# CNC.net
KiCad netlist of a schematic drawn in Altium Designer
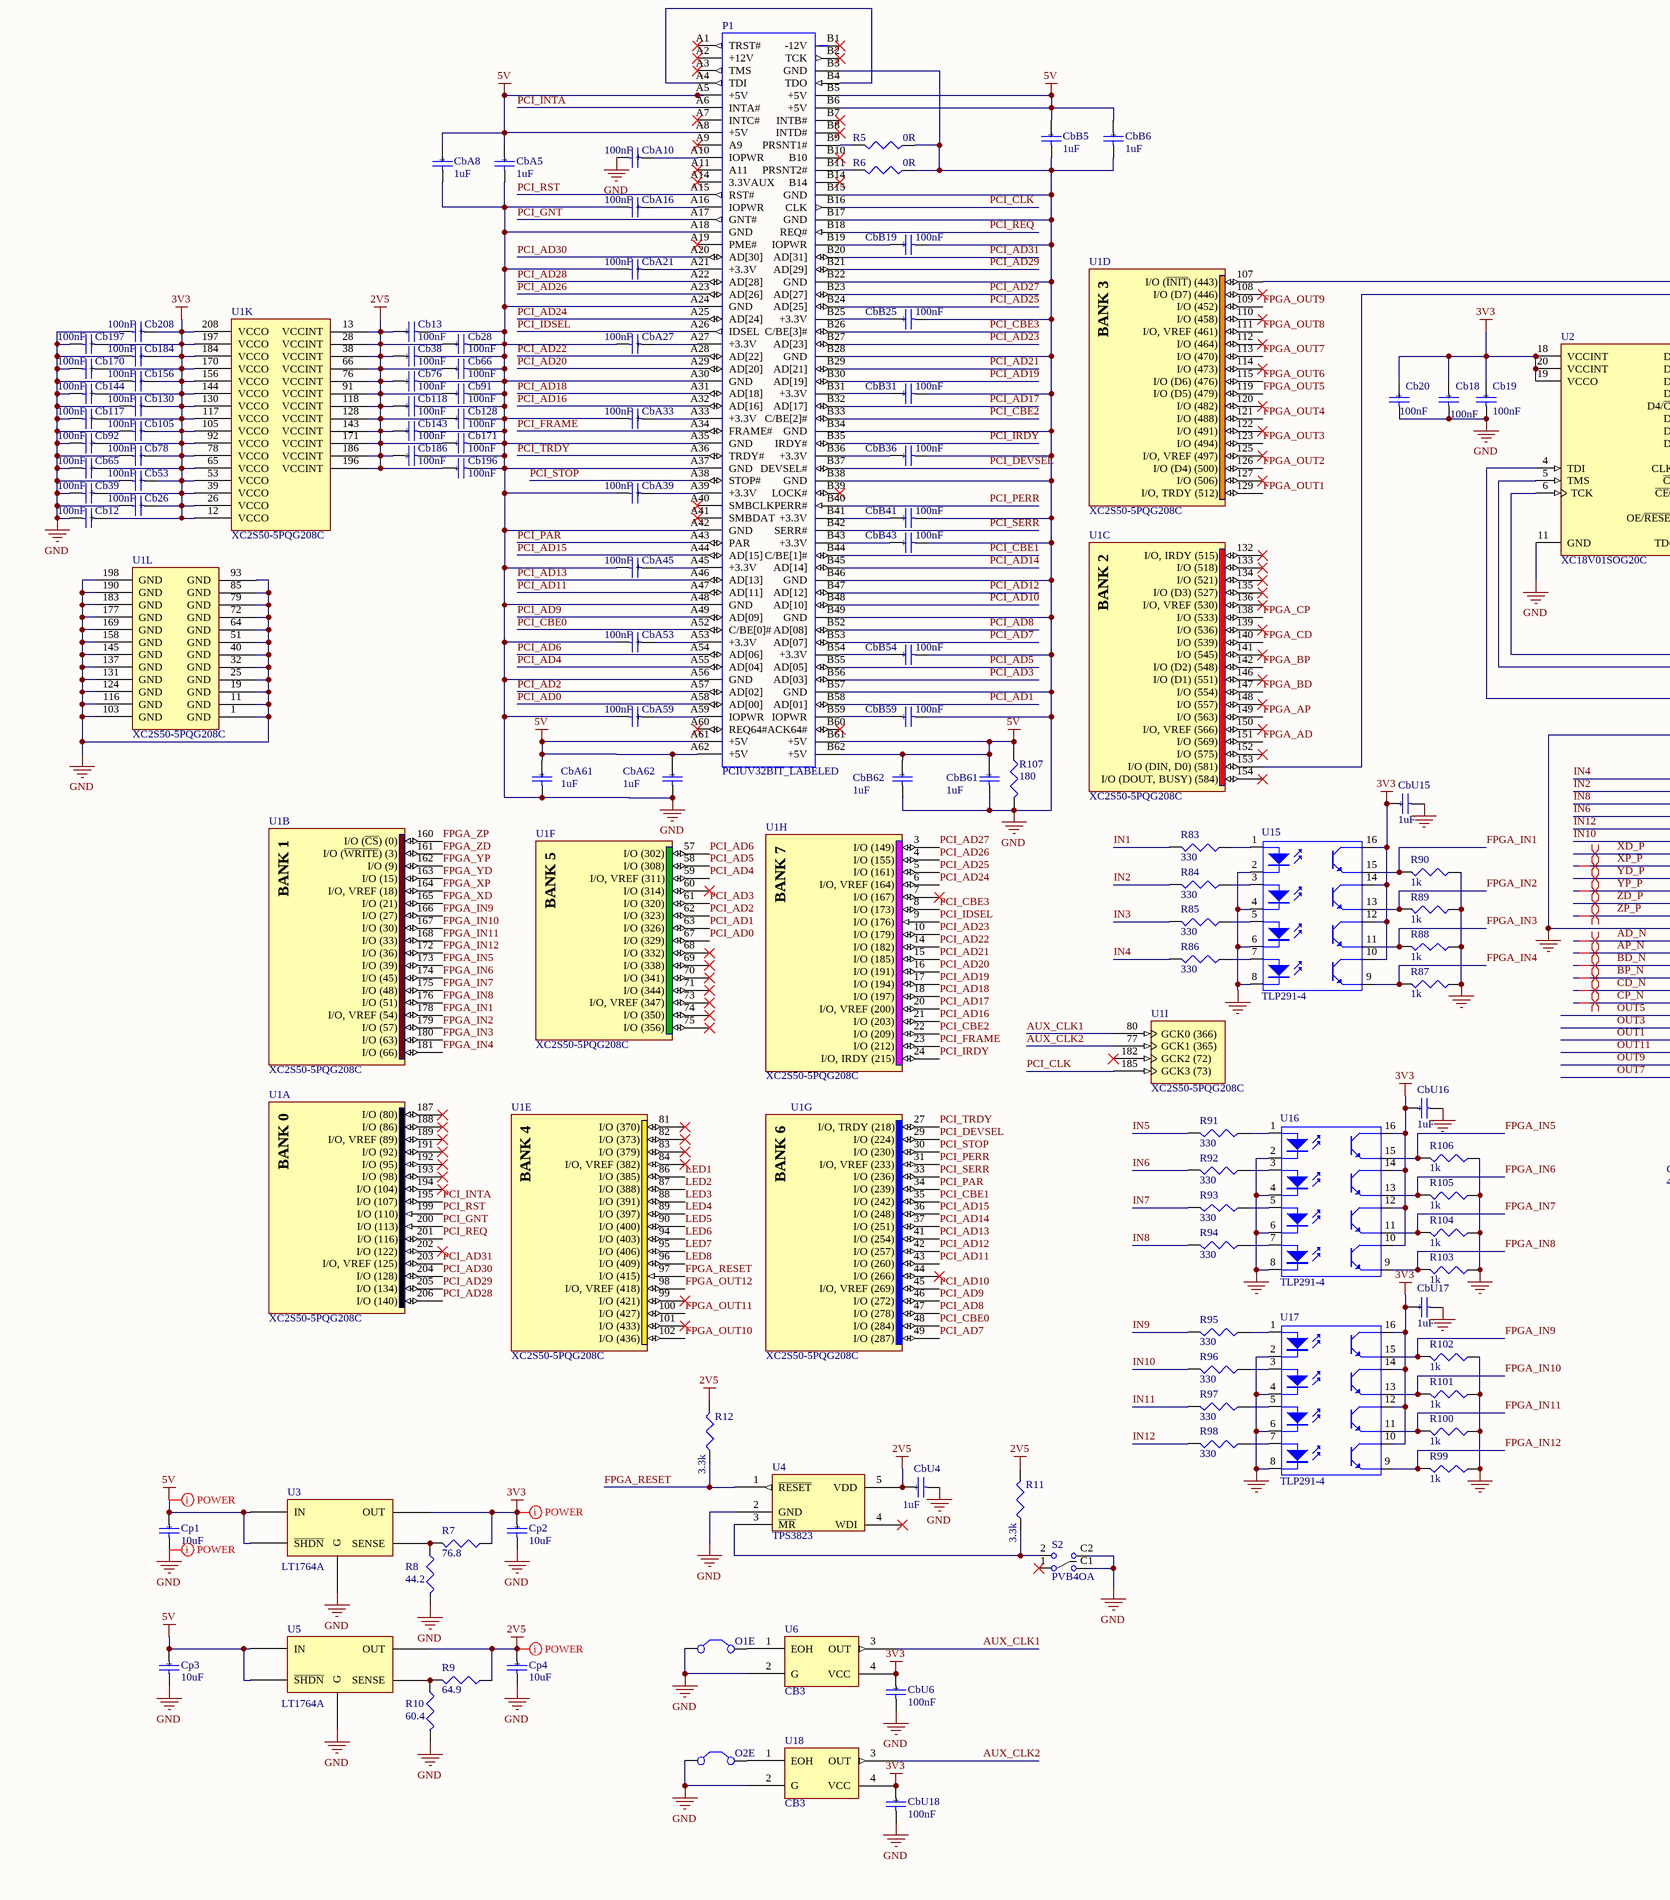
[diagram p0: CNC.SchDoc, bottom left]
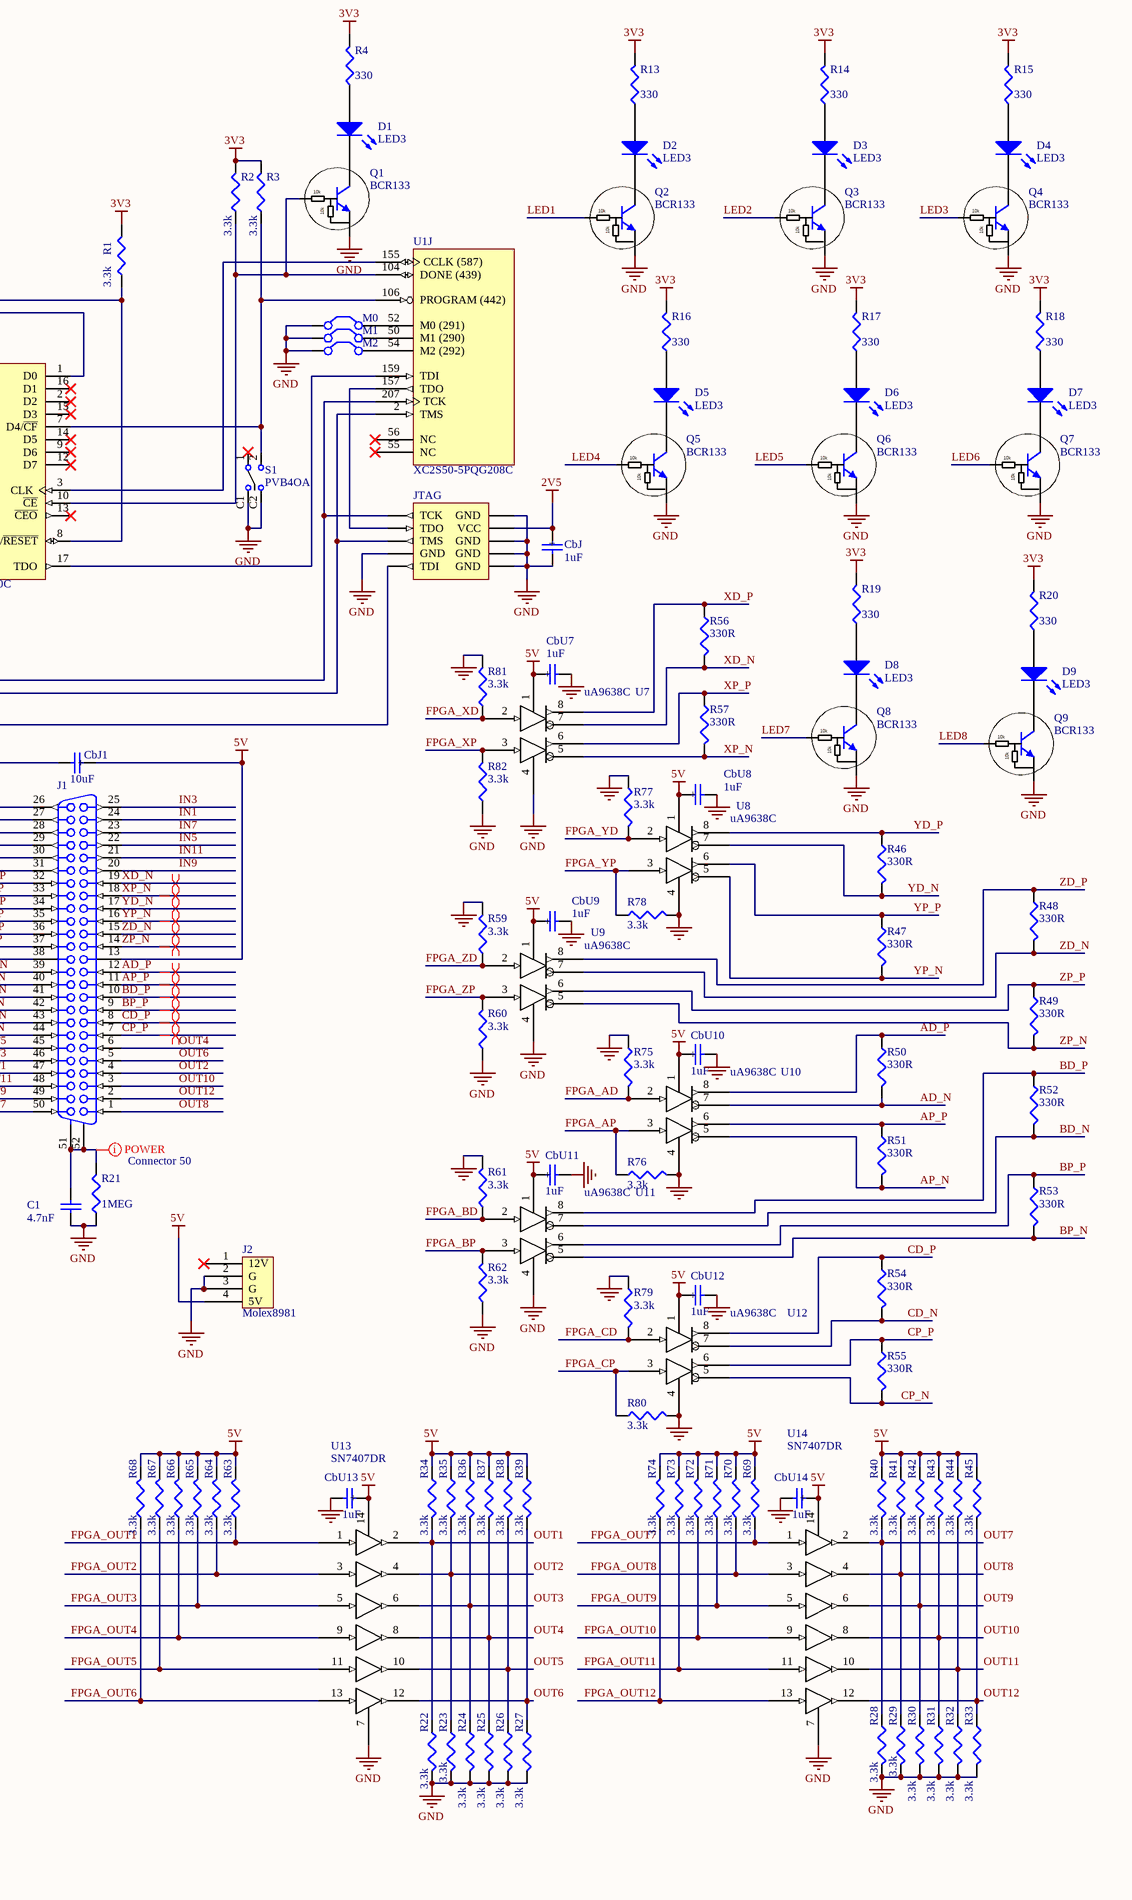
[diagram p1: CNC.SchDoc, bottom right]

(export (version "E")
  (design (tool "Eeschema 10.0.6"))
  (components
    (comp (ref "C1")
      (value "4.7nF")
      (footprint "C1206")
      (description "Capacitor (Semiconductor SIM Model)")
      (fields (field (name "PUBLISHER") "Altium Limited"))
      (libsource (lib "") (part "Cap Semi_1"))
    )
    (comp (ref "Cb12")
      (value "100nF")
      (footprint "C1206_POL")
      (description "Capacitor (Semiconductor SIM Model)")
      (fields (field (name "PUBLISHER") "Altium Limited"))
      (libsource (lib "Miscellaneous Devices") (part "Cap Semi"))
    )
    (comp (ref "Cb13")
      (value "100nF")
      (footprint "C1206_POL")
      (description "Capacitor (Semiconductor SIM Model)")
      (fields (field (name "PUBLISHER") "Altium Limited"))
      (libsource (lib "Miscellaneous Devices") (part "Cap Semi"))
    )
    (comp (ref "Cb18")
      (value "100nF")
      (footprint "C1206_POL")
      (description "Capacitor (Semiconductor SIM Model)")
      (fields (field (name "PUBLISHER") "Altium Limited"))
      (libsource (lib "Miscellaneous Devices") (part "Cap Semi"))
    )
    (comp (ref "Cb19")
      (value "100nF")
      (footprint "C1206_POL")
      (description "Capacitor (Semiconductor SIM Model)")
      (fields (field (name "PUBLISHER") "Altium Limited"))
      (libsource (lib "Miscellaneous Devices") (part "Cap Semi"))
    )
    (comp (ref "Cb20")
      (value "100nF")
      (footprint "C1206_POL")
      (description "Capacitor (Semiconductor SIM Model)")
      (fields (field (name "PUBLISHER") "Altium Limited"))
      (libsource (lib "Miscellaneous Devices") (part "Cap Semi"))
    )
    (comp (ref "Cb26")
      (value "100nF")
      (footprint "C1206_POL")
      (description "Capacitor (Semiconductor SIM Model)")
      (fields (field (name "PUBLISHER") "Altium Limited"))
      (libsource (lib "Miscellaneous Devices") (part "Cap Semi"))
    )
    (comp (ref "Cb28")
      (value "100nF")
      (footprint "C1206_POL")
      (description "Capacitor (Semiconductor SIM Model)")
      (fields (field (name "PUBLISHER") "Altium Limited"))
      (libsource (lib "Miscellaneous Devices") (part "Cap Semi"))
    )
    (comp (ref "Cb38")
      (value "100nF")
      (footprint "C1206_POL")
      (description "Capacitor (Semiconductor SIM Model)")
      (fields (field (name "PUBLISHER") "Altium Limited"))
      (libsource (lib "Miscellaneous Devices") (part "Cap Semi"))
    )
    (comp (ref "Cb39")
      (value "100nF")
      (footprint "C1206_POL")
      (description "Capacitor (Semiconductor SIM Model)")
      (fields (field (name "PUBLISHER") "Altium Limited"))
      (libsource (lib "Miscellaneous Devices") (part "Cap Semi"))
    )
    (comp (ref "Cb53")
      (value "100nF")
      (footprint "C1206_POL")
      (description "Capacitor (Semiconductor SIM Model)")
      (fields (field (name "PUBLISHER") "Altium Limited"))
      (libsource (lib "Miscellaneous Devices") (part "Cap Semi"))
    )
    (comp (ref "Cb65")
      (value "100nF")
      (footprint "C1206_POL")
      (description "Capacitor (Semiconductor SIM Model)")
      (fields (field (name "PUBLISHER") "Altium Limited"))
      (libsource (lib "Miscellaneous Devices") (part "Cap Semi"))
    )
    (comp (ref "Cb66")
      (value "100nF")
      (footprint "C1206_POL")
      (description "Capacitor (Semiconductor SIM Model)")
      (fields (field (name "PUBLISHER") "Altium Limited"))
      (libsource (lib "Miscellaneous Devices") (part "Cap Semi"))
    )
    (comp (ref "Cb76")
      (value "100nF")
      (footprint "C1206_POL")
      (description "Capacitor (Semiconductor SIM Model)")
      (fields (field (name "PUBLISHER") "Altium Limited"))
      (libsource (lib "Miscellaneous Devices") (part "Cap Semi"))
    )
    (comp (ref "Cb78")
      (value "100nF")
      (footprint "C1206_POL")
      (description "Capacitor (Semiconductor SIM Model)")
      (fields (field (name "PUBLISHER") "Altium Limited"))
      (libsource (lib "Miscellaneous Devices") (part "Cap Semi"))
    )
    (comp (ref "Cb91")
      (value "100nF")
      (footprint "C1206_POL")
      (description "Capacitor (Semiconductor SIM Model)")
      (fields (field (name "PUBLISHER") "Altium Limited"))
      (libsource (lib "Miscellaneous Devices") (part "Cap Semi"))
    )
    (comp (ref "Cb92")
      (value "100nF")
      (footprint "C1206_POL")
      (description "Capacitor (Semiconductor SIM Model)")
      (fields (field (name "PUBLISHER") "Altium Limited"))
      (libsource (lib "Miscellaneous Devices") (part "Cap Semi"))
    )
    (comp (ref "Cb105")
      (value "100nF")
      (footprint "C1206_POL")
      (description "Capacitor (Semiconductor SIM Model)")
      (fields (field (name "PUBLISHER") "Altium Limited"))
      (libsource (lib "Miscellaneous Devices") (part "Cap Semi"))
    )
    (comp (ref "Cb117")
      (value "100nF")
      (footprint "C1206_POL")
      (description "Capacitor (Semiconductor SIM Model)")
      (fields (field (name "PUBLISHER") "Altium Limited"))
      (libsource (lib "Miscellaneous Devices") (part "Cap Semi"))
    )
    (comp (ref "Cb118")
      (value "100nF")
      (footprint "C1206_POL")
      (description "Capacitor (Semiconductor SIM Model)")
      (fields (field (name "PUBLISHER") "Altium Limited"))
      (libsource (lib "Miscellaneous Devices") (part "Cap Semi"))
    )
    (comp (ref "Cb128")
      (value "100nF")
      (footprint "C1206_POL")
      (description "Capacitor (Semiconductor SIM Model)")
      (fields (field (name "PUBLISHER") "Altium Limited"))
      (libsource (lib "Miscellaneous Devices") (part "Cap Semi"))
    )
    (comp (ref "Cb130")
      (value "100nF")
      (footprint "C1206_POL")
      (description "Capacitor (Semiconductor SIM Model)")
      (fields (field (name "PUBLISHER") "Altium Limited"))
      (libsource (lib "Miscellaneous Devices") (part "Cap Semi"))
    )
    (comp (ref "Cb143")
      (value "100nF")
      (footprint "C1206_POL")
      (description "Capacitor (Semiconductor SIM Model)")
      (fields (field (name "PUBLISHER") "Altium Limited"))
      (libsource (lib "Miscellaneous Devices") (part "Cap Semi"))
    )
    (comp (ref "Cb144")
      (value "100nF")
      (footprint "C1206_POL")
      (description "Capacitor (Semiconductor SIM Model)")
      (fields (field (name "PUBLISHER") "Altium Limited"))
      (libsource (lib "Miscellaneous Devices") (part "Cap Semi"))
    )
    (comp (ref "Cb156")
      (value "100nF")
      (footprint "C1206_POL")
      (description "Capacitor (Semiconductor SIM Model)")
      (fields (field (name "PUBLISHER") "Altium Limited"))
      (libsource (lib "Miscellaneous Devices") (part "Cap Semi"))
    )
    (comp (ref "Cb170")
      (value "100nF")
      (footprint "C1206_POL")
      (description "Capacitor (Semiconductor SIM Model)")
      (fields (field (name "PUBLISHER") "Altium Limited"))
      (libsource (lib "Miscellaneous Devices") (part "Cap Semi"))
    )
    (comp (ref "Cb171")
      (value "100nF")
      (footprint "C1206_POL")
      (description "Capacitor (Semiconductor SIM Model)")
      (fields (field (name "PUBLISHER") "Altium Limited"))
      (libsource (lib "Miscellaneous Devices") (part "Cap Semi"))
    )
    (comp (ref "Cb184")
      (value "100nF")
      (footprint "C1206_POL")
      (description "Capacitor (Semiconductor SIM Model)")
      (fields (field (name "PUBLISHER") "Altium Limited"))
      (libsource (lib "Miscellaneous Devices") (part "Cap Semi"))
    )
    (comp (ref "Cb186")
      (value "100nF")
      (footprint "C1206_POL")
      (description "Capacitor (Semiconductor SIM Model)")
      (fields (field (name "PUBLISHER") "Altium Limited"))
      (libsource (lib "Miscellaneous Devices") (part "Cap Semi"))
    )
    (comp (ref "Cb196")
      (value "100nF")
      (footprint "C1206_POL")
      (description "Capacitor (Semiconductor SIM Model)")
      (fields (field (name "PUBLISHER") "Altium Limited"))
      (libsource (lib "Miscellaneous Devices") (part "Cap Semi"))
    )
    (comp (ref "Cb197")
      (value "100nF")
      (footprint "C1206_POL")
      (description "Capacitor (Semiconductor SIM Model)")
      (fields (field (name "PUBLISHER") "Altium Limited"))
      (libsource (lib "Miscellaneous Devices") (part "Cap Semi"))
    )
    (comp (ref "Cb208")
      (value "100nF")
      (footprint "C1206_POL")
      (description "Capacitor (Semiconductor SIM Model)")
      (fields (field (name "PUBLISHER") "Altium Limited"))
      (libsource (lib "Miscellaneous Devices") (part "Cap Semi"))
    )
    (comp (ref "CbA5")
      (value "1uF")
      (footprint "C1206_POL")
      (description "Capacitor (Semiconductor SIM Model)")
      (fields (field (name "PUBLISHER") "Altium Limited"))
      (libsource (lib "Miscellaneous Devices") (part "Cap Semi"))
    )
    (comp (ref "CbA8")
      (value "1uF")
      (footprint "C1206_POL")
      (description "Capacitor (Semiconductor SIM Model)")
      (fields (field (name "PUBLISHER") "Altium Limited"))
      (libsource (lib "Miscellaneous Devices") (part "Cap Semi"))
    )
    (comp (ref "CbA10")
      (value "100nF")
      (footprint "C1206_POL")
      (description "Capacitor (Semiconductor SIM Model)")
      (fields (field (name "PUBLISHER") "Altium Limited"))
      (libsource (lib "Miscellaneous Devices") (part "Cap Semi"))
    )
    (comp (ref "CbA16")
      (value "100nF")
      (footprint "C1206_POL")
      (description "Capacitor (Semiconductor SIM Model)")
      (fields (field (name "PUBLISHER") "Altium Limited"))
      (libsource (lib "Miscellaneous Devices") (part "Cap Semi"))
    )
    (comp (ref "CbA21")
      (value "100nF")
      (footprint "C1206_POL")
      (description "Capacitor (Semiconductor SIM Model)")
      (fields (field (name "PUBLISHER") "Altium Limited"))
      (libsource (lib "Miscellaneous Devices") (part "Cap Semi"))
    )
    (comp (ref "CbA27")
      (value "100nF")
      (footprint "C1206_POL")
      (description "Capacitor (Semiconductor SIM Model)")
      (fields (field (name "PUBLISHER") "Altium Limited"))
      (libsource (lib "Miscellaneous Devices") (part "Cap Semi"))
    )
    (comp (ref "CbA33")
      (value "100nF")
      (footprint "C1206_POL")
      (description "Capacitor (Semiconductor SIM Model)")
      (fields (field (name "PUBLISHER") "Altium Limited"))
      (libsource (lib "Miscellaneous Devices") (part "Cap Semi"))
    )
    (comp (ref "CbA39")
      (value "100nF")
      (footprint "C1206_POL")
      (description "Capacitor (Semiconductor SIM Model)")
      (fields (field (name "PUBLISHER") "Altium Limited"))
      (libsource (lib "Miscellaneous Devices") (part "Cap Semi"))
    )
    (comp (ref "CbA45")
      (value "100nF")
      (footprint "C1206_POL")
      (description "Capacitor (Semiconductor SIM Model)")
      (fields (field (name "PUBLISHER") "Altium Limited"))
      (libsource (lib "Miscellaneous Devices") (part "Cap Semi"))
    )
    (comp (ref "CbA53")
      (value "100nF")
      (footprint "C1206_POL")
      (description "Capacitor (Semiconductor SIM Model)")
      (fields (field (name "PUBLISHER") "Altium Limited"))
      (libsource (lib "Miscellaneous Devices") (part "Cap Semi"))
    )
    (comp (ref "CbA59")
      (value "100nF")
      (footprint "C1206_POL")
      (description "Capacitor (Semiconductor SIM Model)")
      (fields (field (name "PUBLISHER") "Altium Limited"))
      (libsource (lib "Miscellaneous Devices") (part "Cap Semi"))
    )
    (comp (ref "CbA61")
      (value "1uF")
      (footprint "C1206_POL")
      (description "Capacitor (Semiconductor SIM Model)")
      (fields (field (name "PUBLISHER") "Altium Limited"))
      (libsource (lib "Miscellaneous Devices") (part "Cap Semi"))
    )
    (comp (ref "CbA62")
      (value "1uF")
      (footprint "C1206_POL")
      (description "Capacitor (Semiconductor SIM Model)")
      (fields (field (name "PUBLISHER") "Altium Limited"))
      (libsource (lib "Miscellaneous Devices") (part "Cap Semi"))
    )
    (comp (ref "CbB5")
      (value "1uF")
      (footprint "C1206_POL")
      (description "Capacitor (Semiconductor SIM Model)")
      (fields (field (name "PUBLISHER") "Altium Limited"))
      (libsource (lib "Miscellaneous Devices") (part "Cap Semi"))
    )
    (comp (ref "CbB6")
      (value "1uF")
      (footprint "C1206_POL")
      (description "Capacitor (Semiconductor SIM Model)")
      (fields (field (name "PUBLISHER") "Altium Limited"))
      (libsource (lib "Miscellaneous Devices") (part "Cap Semi"))
    )
    (comp (ref "CbB19")
      (value "100nF")
      (footprint "C1206_POL")
      (description "Capacitor (Semiconductor SIM Model)")
      (fields (field (name "PUBLISHER") "Altium Limited"))
      (libsource (lib "Miscellaneous Devices") (part "Cap Semi"))
    )
    (comp (ref "CbB25")
      (value "100nF")
      (footprint "C1206_POL")
      (description "Capacitor (Semiconductor SIM Model)")
      (fields (field (name "PUBLISHER") "Altium Limited"))
      (libsource (lib "Miscellaneous Devices") (part "Cap Semi"))
    )
    (comp (ref "CbB31")
      (value "100nF")
      (footprint "C1206_POL")
      (description "Capacitor (Semiconductor SIM Model)")
      (fields (field (name "PUBLISHER") "Altium Limited"))
      (libsource (lib "Miscellaneous Devices") (part "Cap Semi"))
    )
    (comp (ref "CbB36")
      (value "100nF")
      (footprint "C1206_POL")
      (description "Capacitor (Semiconductor SIM Model)")
      (fields (field (name "PUBLISHER") "Altium Limited"))
      (libsource (lib "Miscellaneous Devices") (part "Cap Semi"))
    )
    (comp (ref "CbB41")
      (value "100nF")
      (footprint "C1206_POL")
      (description "Capacitor (Semiconductor SIM Model)")
      (fields (field (name "PUBLISHER") "Altium Limited"))
      (libsource (lib "Miscellaneous Devices") (part "Cap Semi"))
    )
    (comp (ref "CbB43")
      (value "100nF")
      (footprint "C1206_POL")
      (description "Capacitor (Semiconductor SIM Model)")
      (fields (field (name "PUBLISHER") "Altium Limited"))
      (libsource (lib "Miscellaneous Devices") (part "Cap Semi"))
    )
    (comp (ref "CbB54")
      (value "100nF")
      (footprint "C1206_POL")
      (description "Capacitor (Semiconductor SIM Model)")
      (fields (field (name "PUBLISHER") "Altium Limited"))
      (libsource (lib "Miscellaneous Devices") (part "Cap Semi"))
    )
    (comp (ref "CbB59")
      (value "100nF")
      (footprint "C1206_POL")
      (description "Capacitor (Semiconductor SIM Model)")
      (fields (field (name "PUBLISHER") "Altium Limited"))
      (libsource (lib "Miscellaneous Devices") (part "Cap Semi"))
    )
    (comp (ref "CbB61")
      (value "1uF")
      (footprint "C1206_POL")
      (description "Capacitor (Semiconductor SIM Model)")
      (fields (field (name "PUBLISHER") "Altium Limited"))
      (libsource (lib "Miscellaneous Devices") (part "Cap Semi"))
    )
    (comp (ref "CbB62")
      (value "1uF")
      (footprint "C1206_POL")
      (description "Capacitor (Semiconductor SIM Model)")
      (fields (field (name "PUBLISHER") "Altium Limited"))
      (libsource (lib "Miscellaneous Devices") (part "Cap Semi"))
    )
    (comp (ref "CbJ")
      (value "1uF")
      (footprint "C1206_POL")
      (description "Capacitor (Semiconductor SIM Model)")
      (fields (field (name "PUBLISHER") "Altium Limited"))
      (libsource (lib "Miscellaneous Devices") (part "Cap Semi"))
    )
    (comp (ref "CbJ1")
      (value "10uF")
      (footprint "C1206_POL")
      (description "Capacitor (Semiconductor SIM Model)")
      (fields (field (name "PUBLISHER") "Altium Limited"))
      (libsource (lib "Miscellaneous Devices") (part "Cap Semi"))
    )
    (comp (ref "CbU4")
      (value "1uF")
      (footprint "C1206_POL")
      (description "Capacitor (Semiconductor SIM Model)")
      (fields (field (name "PUBLISHER") "Altium Limited"))
      (libsource (lib "Miscellaneous Devices") (part "Cap Semi"))
    )
    (comp (ref "CbU6")
      (value "100nF")
      (footprint "C1206_POL")
      (description "Capacitor (Semiconductor SIM Model)")
      (fields (field (name "PUBLISHER") "Altium Limited"))
      (libsource (lib "Miscellaneous Devices") (part "Cap Semi"))
    )
    (comp (ref "CbU7")
      (value "1uF")
      (footprint "C1206_POL")
      (description "Capacitor (Semiconductor SIM Model)")
      (fields (field (name "PUBLISHER") "Altium Limited"))
      (libsource (lib "Miscellaneous Devices") (part "Cap Semi"))
    )
    (comp (ref "CbU8")
      (value "1uF")
      (footprint "C1206_POL")
      (description "Capacitor (Semiconductor SIM Model)")
      (fields (field (name "PUBLISHER") "Altium Limited"))
      (libsource (lib "Miscellaneous Devices") (part "Cap Semi"))
    )
    (comp (ref "CbU9")
      (value "1uF")
      (footprint "C1206_POL")
      (description "Capacitor (Semiconductor SIM Model)")
      (fields (field (name "PUBLISHER") "Altium Limited"))
      (libsource (lib "Miscellaneous Devices") (part "Cap Semi"))
    )
    (comp (ref "CbU10")
      (value "1uF")
      (footprint "C1206_POL")
      (description "Capacitor (Semiconductor SIM Model)")
      (fields (field (name "PUBLISHER") "Altium Limited"))
      (libsource (lib "Miscellaneous Devices") (part "Cap Semi"))
    )
    (comp (ref "CbU11")
      (value "1uF")
      (footprint "C1206_POL")
      (description "Capacitor (Semiconductor SIM Model)")
      (fields (field (name "PUBLISHER") "Altium Limited"))
      (libsource (lib "Miscellaneous Devices") (part "Cap Semi"))
    )
    (comp (ref "CbU12")
      (value "1uF")
      (footprint "C1206_POL")
      (description "Capacitor (Semiconductor SIM Model)")
      (fields (field (name "PUBLISHER") "Altium Limited"))
      (libsource (lib "Miscellaneous Devices") (part "Cap Semi"))
    )
    (comp (ref "CbU13")
      (value "1uF")
      (footprint "C1206_POL")
      (description "Capacitor (Semiconductor SIM Model)")
      (fields (field (name "PUBLISHER") "Altium Limited"))
      (libsource (lib "Miscellaneous Devices") (part "Cap Semi"))
    )
    (comp (ref "CbU14")
      (value "1uF")
      (footprint "C1206_POL")
      (description "Capacitor (Semiconductor SIM Model)")
      (fields (field (name "PUBLISHER") "Altium Limited"))
      (libsource (lib "Miscellaneous Devices") (part "Cap Semi"))
    )
    (comp (ref "CbU15")
      (value "1uF")
      (footprint "C1206_POL")
      (description "Capacitor (Semiconductor SIM Model)")
      (fields (field (name "PUBLISHER") "Altium Limited"))
      (libsource (lib "Miscellaneous Devices") (part "Cap Semi"))
    )
    (comp (ref "CbU16")
      (value "1uF")
      (footprint "C1206_POL")
      (description "Capacitor (Semiconductor SIM Model)")
      (fields (field (name "PUBLISHER") "Altium Limited"))
      (libsource (lib "Miscellaneous Devices") (part "Cap Semi"))
    )
    (comp (ref "CbU17")
      (value "1uF")
      (footprint "C1206_POL")
      (description "Capacitor (Semiconductor SIM Model)")
      (fields (field (name "PUBLISHER") "Altium Limited"))
      (libsource (lib "Miscellaneous Devices") (part "Cap Semi"))
    )
    (comp (ref "CbU18")
      (value "100nF")
      (footprint "C1206_POL")
      (description "Capacitor (Semiconductor SIM Model)")
      (fields (field (name "PUBLISHER") "Altium Limited"))
      (libsource (lib "Miscellaneous Devices") (part "Cap Semi"))
    )
    (comp (ref "Cp1")
      (value "10uF")
      (footprint "C1206_POL")
      (description "Capacitor (Semiconductor SIM Model)")
      (fields (field (name "PUBLISHER") "Altium Limited"))
      (libsource (lib "Miscellaneous Devices") (part "Cap Semi"))
    )
    (comp (ref "Cp2")
      (value "10uF")
      (footprint "C1206_POL")
      (description "Capacitor (Semiconductor SIM Model)")
      (fields (field (name "PUBLISHER") "Altium Limited"))
      (libsource (lib "Miscellaneous Devices") (part "Cap Semi"))
    )
    (comp (ref "Cp3")
      (value "10uF")
      (footprint "C1206_POL")
      (description "Capacitor (Semiconductor SIM Model)")
      (fields (field (name "PUBLISHER") "Altium Limited"))
      (libsource (lib "Miscellaneous Devices") (part "Cap Semi"))
    )
    (comp (ref "Cp4")
      (value "10uF")
      (footprint "C1206_POL")
      (description "Capacitor (Semiconductor SIM Model)")
      (fields (field (name "PUBLISHER") "Altium Limited"))
      (libsource (lib "Miscellaneous Devices") (part "Cap Semi"))
    )
    (comp (ref "D1")
      (value "LED3")
      (footprint "3.5X2.8X1.9")
      (description "Typical BLUE SiC LED")
      (fields (field (name "PUBLISHER") "Altium Limited"))
      (libsource (lib "Miscellaneous Devices") (part "LED3"))
    )
    (comp (ref "D2")
      (value "LED3")
      (footprint "3.5X2.8X1.9")
      (description "Typical BLUE SiC LED")
      (fields (field (name "PUBLISHER") "Altium Limited"))
      (libsource (lib "Miscellaneous Devices") (part "LED3"))
    )
    (comp (ref "D3")
      (value "LED3")
      (footprint "3.5X2.8X1.9")
      (description "Typical BLUE SiC LED")
      (fields (field (name "PUBLISHER") "Altium Limited"))
      (libsource (lib "Miscellaneous Devices") (part "LED3"))
    )
    (comp (ref "D4")
      (value "LED3")
      (footprint "3.5X2.8X1.9")
      (description "Typical BLUE SiC LED")
      (fields (field (name "PUBLISHER") "Altium Limited"))
      (libsource (lib "Miscellaneous Devices") (part "LED3"))
    )
    (comp (ref "D5")
      (value "LED3")
      (footprint "3.5X2.8X1.9")
      (description "Typical BLUE SiC LED")
      (fields (field (name "PUBLISHER") "Altium Limited"))
      (libsource (lib "Miscellaneous Devices") (part "LED3"))
    )
    (comp (ref "D6")
      (value "LED3")
      (footprint "3.5X2.8X1.9")
      (description "Typical BLUE SiC LED")
      (fields (field (name "PUBLISHER") "Altium Limited"))
      (libsource (lib "Miscellaneous Devices") (part "LED3"))
    )
    (comp (ref "D7")
      (value "LED3")
      (footprint "3.5X2.8X1.9")
      (description "Typical BLUE SiC LED")
      (fields (field (name "PUBLISHER") "Altium Limited"))
      (libsource (lib "Miscellaneous Devices") (part "LED3"))
    )
    (comp (ref "D8")
      (value "LED3")
      (footprint "3.5X2.8X1.9")
      (description "Typical BLUE SiC LED")
      (fields (field (name "PUBLISHER") "Altium Limited"))
      (libsource (lib "Miscellaneous Devices") (part "LED3"))
    )
    (comp (ref "D9")
      (value "LED3")
      (footprint "3.5X2.8X1.9")
      (description "Typical BLUE SiC LED")
      (fields (field (name "PUBLISHER") "Altium Limited"))
      (libsource (lib "Miscellaneous Devices") (part "LED3"))
    )
    (comp (ref "J1")
      (value "Connector 50")
      (footprint "SCSI50")
      (description "Receptacle Header Assemby")
      (fields (field (name "PUBLISHER") "Altium Limited"))
      (libsource (lib "Miscellaneous Connectors") (part "Connector 50"))
    )
    (comp (ref "J2")
      (value "Molex8981")
      (footprint "molex8981")
      (libsource (lib "Connectors") (part "Molex8981"))
    )
    (comp (ref "JTAG")
      (value "JTAG")
      (footprint "HDR2X5")
      (description "Header, 5-Pin, Dual row")
      (fields (field (name "PUBLISHER") "Altium Limited"))
      (libsource (lib "Connectors") (part "JTAG"))
    )
    (comp (ref "M0")
      (value "M0")
      (footprint "RAD-0.2")
      (description "Jumper Wire")
      (fields (field (name "PUBLISHER") "Altium Limited"))
      (libsource (lib "Miscellaneous Devices") (part "Jumper"))
    )
    (comp (ref "M1")
      (value "M0")
      (footprint "RAD-0.2")
      (description "Jumper Wire")
      (fields (field (name "PUBLISHER") "Altium Limited"))
      (libsource (lib "Miscellaneous Devices") (part "Jumper"))
    )
    (comp (ref "M2")
      (value "M0")
      (footprint "RAD-0.2")
      (description "Jumper Wire")
      (fields (field (name "PUBLISHER") "Altium Limited"))
      (libsource (lib "Miscellaneous Devices") (part "Jumper"))
    )
    (comp (ref "O1E")
      (value "M0")
      (footprint "RAD-0.2")
      (description "Jumper Wire")
      (fields (field (name "PUBLISHER") "Altium Limited"))
      (libsource (lib "Miscellaneous Devices") (part "Jumper"))
    )
    (comp (ref "O2E")
      (value "M0")
      (footprint "RAD-0.2")
      (description "Jumper Wire")
      (fields (field (name "PUBLISHER") "Altium Limited"))
      (libsource (lib "Miscellaneous Devices") (part "Jumper"))
    )
    (comp (ref "P1")
      (value "PCIUV32BIT_LABELED")
      (footprint "PCIUV32BIT")
      (description "Card, 116-Position")
      (libsource (lib "Connectors") (part "PCIUV32BIT_LABELED"))
    )
    (comp (ref "Q1")
      (value "BCR133")
      (footprint "SOT-23B_L")
      (description "NPN Bipolar Transistor")
      (fields (field (name "PUBLISHER") "Altium Limited"))
      (libsource (lib "Connectors") (part "BCR133"))
    )
    (comp (ref "Q2")
      (value "BCR133")
      (footprint "SOT-23B_L")
      (description "NPN Bipolar Transistor")
      (fields (field (name "PUBLISHER") "Altium Limited"))
      (libsource (lib "Connectors") (part "BCR133"))
    )
    (comp (ref "Q3")
      (value "BCR133")
      (footprint "SOT-23B_L")
      (description "NPN Bipolar Transistor")
      (fields (field (name "PUBLISHER") "Altium Limited"))
      (libsource (lib "Connectors") (part "BCR133"))
    )
    (comp (ref "Q4")
      (value "BCR133")
      (footprint "SOT-23B_L")
      (description "NPN Bipolar Transistor")
      (fields (field (name "PUBLISHER") "Altium Limited"))
      (libsource (lib "Connectors") (part "BCR133"))
    )
    (comp (ref "Q5")
      (value "BCR133")
      (footprint "SOT-23B_L")
      (description "NPN Bipolar Transistor")
      (fields (field (name "PUBLISHER") "Altium Limited"))
      (libsource (lib "Connectors") (part "BCR133"))
    )
    (comp (ref "Q6")
      (value "BCR133")
      (footprint "SOT-23B_L")
      (description "NPN Bipolar Transistor")
      (fields (field (name "PUBLISHER") "Altium Limited"))
      (libsource (lib "Connectors") (part "BCR133"))
    )
    (comp (ref "Q7")
      (value "BCR133")
      (footprint "SOT-23B_L")
      (description "NPN Bipolar Transistor")
      (fields (field (name "PUBLISHER") "Altium Limited"))
      (libsource (lib "Connectors") (part "BCR133"))
    )
    (comp (ref "Q8")
      (value "BCR133")
      (footprint "SOT-23B_L")
      (description "NPN Bipolar Transistor")
      (fields (field (name "PUBLISHER") "Altium Limited"))
      (libsource (lib "Connectors") (part "BCR133"))
    )
    (comp (ref "Q9")
      (value "BCR133")
      (footprint "SOT-23B_L")
      (description "NPN Bipolar Transistor")
      (fields (field (name "PUBLISHER") "Altium Limited"))
      (libsource (lib "Connectors") (part "BCR133"))
    )
    (comp (ref "R1")
      (value "3.3k")
      (footprint "J1-0603")
      (description "Resistor")
      (fields (field (name "PUBLISHER") "Altium Limited"))
      (libsource (lib "Miscellaneous Devices") (part "Res3"))
    )
    (comp (ref "R2")
      (value "3.3k")
      (footprint "J1-0603")
      (description "Resistor")
      (fields (field (name "PUBLISHER") "Altium Limited"))
      (libsource (lib "Miscellaneous Devices") (part "Res3"))
    )
    (comp (ref "R3")
      (value "3.3k")
      (footprint "J1-0603")
      (description "Resistor")
      (fields (field (name "PUBLISHER") "Altium Limited"))
      (libsource (lib "Miscellaneous Devices") (part "Res3"))
    )
    (comp (ref "R4")
      (value "330")
      (footprint "J1-0603")
      (description "Resistor")
      (fields (field (name "Comment") "330R") (field (name "PUBLISHER") "Altium Limited"))
      (libsource (lib "Miscellaneous Devices") (part "Res3"))
    )
    (comp (ref "R5")
      (value "0R")
      (footprint "J1-0603")
      (description "Resistor")
      (fields (field (name "PUBLISHER") "Altium Limited"))
      (libsource (lib "Miscellaneous Devices") (part "Res3"))
    )
    (comp (ref "R6")
      (value "0R")
      (footprint "J1-0603")
      (description "Resistor")
      (fields (field (name "PUBLISHER") "Altium Limited"))
      (libsource (lib "Miscellaneous Devices") (part "Res3"))
    )
    (comp (ref "R7")
      (value "76.8")
      (footprint "14-1210")
      (description "Resistor")
      (fields (field (name "Comment") "76.8R1%") (field (name "PUBLISHER") "Altium Limited"))
      (libsource (lib "Miscellaneous Devices") (part "Res3"))
    )
    (comp (ref "R8")
      (value "44.2")
      (footprint "14-1210")
      (description "Resistor")
      (fields (field (name "Comment") "44.2R1%") (field (name "PUBLISHER") "Altium Limited"))
      (libsource (lib "Miscellaneous Devices") (part "Res3"))
    )
    (comp (ref "R9")
      (value "64.9")
      (footprint "14-1210")
      (description "Resistor")
      (fields (field (name "Comment") "64.9R1%") (field (name "PUBLISHER") "Altium Limited"))
      (libsource (lib "Miscellaneous Devices") (part "Res3"))
    )
    (comp (ref "R10")
      (value "60.4")
      (footprint "14-1210")
      (description "Resistor")
      (fields (field (name "Comment") "60.4R1%") (field (name "PUBLISHER") "Altium Limited"))
      (libsource (lib "Miscellaneous Devices") (part "Res3"))
    )
    (comp (ref "R11")
      (value "3.3k")
      (footprint "J1-0603")
      (description "Resistor")
      (fields (field (name "PUBLISHER") "Altium Limited"))
      (libsource (lib "Miscellaneous Devices") (part "Res3"))
    )
    (comp (ref "R12")
      (value "3.3k")
      (footprint "J1-0603")
      (description "Resistor")
      (fields (field (name "PUBLISHER") "Altium Limited"))
      (libsource (lib "Miscellaneous Devices") (part "Res3"))
    )
    (comp (ref "R13")
      (value "330")
      (footprint "J1-0603")
      (description "Resistor")
      (fields (field (name "Comment") "330R") (field (name "PUBLISHER") "Altium Limited"))
      (libsource (lib "Miscellaneous Devices") (part "Res3"))
    )
    (comp (ref "R14")
      (value "330")
      (footprint "J1-0603")
      (description "Resistor")
      (fields (field (name "Comment") "330R") (field (name "PUBLISHER") "Altium Limited"))
      (libsource (lib "Miscellaneous Devices") (part "Res3"))
    )
    (comp (ref "R15")
      (value "330")
      (footprint "J1-0603")
      (description "Resistor")
      (fields (field (name "Comment") "330R") (field (name "PUBLISHER") "Altium Limited"))
      (libsource (lib "Miscellaneous Devices") (part "Res3"))
    )
    (comp (ref "R16")
      (value "330")
      (footprint "J1-0603")
      (description "Resistor")
      (fields (field (name "Comment") "330R") (field (name "PUBLISHER") "Altium Limited"))
      (libsource (lib "Miscellaneous Devices") (part "Res3"))
    )
    (comp (ref "R17")
      (value "330")
      (footprint "J1-0603")
      (description "Resistor")
      (fields (field (name "Comment") "330R") (field (name "PUBLISHER") "Altium Limited"))
      (libsource (lib "Miscellaneous Devices") (part "Res3"))
    )
    (comp (ref "R18")
      (value "330")
      (footprint "J1-0603")
      (description "Resistor")
      (fields (field (name "Comment") "330R") (field (name "PUBLISHER") "Altium Limited"))
      (libsource (lib "Miscellaneous Devices") (part "Res3"))
    )
    (comp (ref "R19")
      (value "330")
      (footprint "J1-0603")
      (description "Resistor")
      (fields (field (name "Comment") "330R") (field (name "PUBLISHER") "Altium Limited"))
      (libsource (lib "Miscellaneous Devices") (part "Res3"))
    )
    (comp (ref "R20")
      (value "330")
      (footprint "J1-0603")
      (description "Resistor")
      (fields (field (name "Comment") "330R") (field (name "PUBLISHER") "Altium Limited"))
      (libsource (lib "Miscellaneous Devices") (part "Res3"))
    )
    (comp (ref "R21")
      (value "1MEG")
      (footprint "J1-0603")
      (description "Resistor")
      (fields (field (name "Comment") "1M") (field (name "PUBLISHER") "Altium Limited"))
      (libsource (lib "Miscellaneous Devices") (part "Res3"))
    )
    (comp (ref "R22")
      (value "3.3k")
      (footprint "J1-0603")
      (description "Resistor")
      (fields (field (name "PUBLISHER") "Altium Limited"))
      (libsource (lib "Miscellaneous Devices") (part "Res3"))
    )
    (comp (ref "R23")
      (value "3.3k")
      (footprint "J1-0603")
      (description "Resistor")
      (fields (field (name "PUBLISHER") "Altium Limited"))
      (libsource (lib "Miscellaneous Devices") (part "Res3"))
    )
    (comp (ref "R24")
      (value "3.3k")
      (footprint "J1-0603")
      (description "Resistor")
      (fields (field (name "PUBLISHER") "Altium Limited"))
      (libsource (lib "Miscellaneous Devices") (part "Res3"))
    )
    (comp (ref "R25")
      (value "3.3k")
      (footprint "J1-0603")
      (description "Resistor")
      (fields (field (name "PUBLISHER") "Altium Limited"))
      (libsource (lib "Miscellaneous Devices") (part "Res3"))
    )
    (comp (ref "R26")
      (value "3.3k")
      (footprint "J1-0603")
      (description "Resistor")
      (fields (field (name "PUBLISHER") "Altium Limited"))
      (libsource (lib "Miscellaneous Devices") (part "Res3"))
    )
    (comp (ref "R27")
      (value "3.3k")
      (footprint "J1-0603")
      (description "Resistor")
      (fields (field (name "PUBLISHER") "Altium Limited"))
      (libsource (lib "Miscellaneous Devices") (part "Res3"))
    )
    (comp (ref "R28")
      (value "3.3k")
      (footprint "J1-0603")
      (description "Resistor")
      (fields (field (name "PUBLISHER") "Altium Limited"))
      (libsource (lib "Miscellaneous Devices") (part "Res3"))
    )
    (comp (ref "R29")
      (value "3.3k")
      (footprint "J1-0603")
      (description "Resistor")
      (fields (field (name "PUBLISHER") "Altium Limited"))
      (libsource (lib "Miscellaneous Devices") (part "Res3"))
    )
    (comp (ref "R30")
      (value "3.3k")
      (footprint "J1-0603")
      (description "Resistor")
      (fields (field (name "PUBLISHER") "Altium Limited"))
      (libsource (lib "Miscellaneous Devices") (part "Res3"))
    )
    (comp (ref "R31")
      (value "3.3k")
      (footprint "J1-0603")
      (description "Resistor")
      (fields (field (name "PUBLISHER") "Altium Limited"))
      (libsource (lib "Miscellaneous Devices") (part "Res3"))
    )
    (comp (ref "R32")
      (value "3.3k")
      (footprint "J1-0603")
      (description "Resistor")
      (fields (field (name "PUBLISHER") "Altium Limited"))
      (libsource (lib "Miscellaneous Devices") (part "Res3"))
    )
    (comp (ref "R33")
      (value "3.3k")
      (footprint "J1-0603")
      (description "Resistor")
      (fields (field (name "PUBLISHER") "Altium Limited"))
      (libsource (lib "Miscellaneous Devices") (part "Res3"))
    )
    (comp (ref "R34")
      (value "3.3k")
      (footprint "J1-0603")
      (description "Resistor")
      (fields (field (name "PUBLISHER") "Altium Limited"))
      (libsource (lib "Miscellaneous Devices") (part "Res3"))
    )
    (comp (ref "R35")
      (value "3.3k")
      (footprint "J1-0603")
      (description "Resistor")
      (fields (field (name "PUBLISHER") "Altium Limited"))
      (libsource (lib "Miscellaneous Devices") (part "Res3"))
    )
    (comp (ref "R36")
      (value "3.3k")
      (footprint "J1-0603")
      (description "Resistor")
      (fields (field (name "PUBLISHER") "Altium Limited"))
      (libsource (lib "Miscellaneous Devices") (part "Res3"))
    )
    (comp (ref "R37")
      (value "3.3k")
      (footprint "J1-0603")
      (description "Resistor")
      (fields (field (name "PUBLISHER") "Altium Limited"))
      (libsource (lib "Miscellaneous Devices") (part "Res3"))
    )
    (comp (ref "R38")
      (value "3.3k")
      (footprint "J1-0603")
      (description "Resistor")
      (fields (field (name "PUBLISHER") "Altium Limited"))
      (libsource (lib "Miscellaneous Devices") (part "Res3"))
    )
    (comp (ref "R39")
      (value "3.3k")
      (footprint "J1-0603")
      (description "Resistor")
      (fields (field (name "PUBLISHER") "Altium Limited"))
      (libsource (lib "Miscellaneous Devices") (part "Res3"))
    )
    (comp (ref "R40")
      (value "3.3k")
      (footprint "J1-0603")
      (description "Resistor")
      (fields (field (name "PUBLISHER") "Altium Limited"))
      (libsource (lib "Miscellaneous Devices") (part "Res3"))
    )
    (comp (ref "R41")
      (value "3.3k")
      (footprint "J1-0603")
      (description "Resistor")
      (fields (field (name "PUBLISHER") "Altium Limited"))
      (libsource (lib "Miscellaneous Devices") (part "Res3"))
    )
    (comp (ref "R42")
      (value "3.3k")
      (footprint "J1-0603")
      (description "Resistor")
      (fields (field (name "PUBLISHER") "Altium Limited"))
      (libsource (lib "Miscellaneous Devices") (part "Res3"))
    )
    (comp (ref "R43")
      (value "3.3k")
      (footprint "J1-0603")
      (description "Resistor")
      (fields (field (name "PUBLISHER") "Altium Limited"))
      (libsource (lib "Miscellaneous Devices") (part "Res3"))
    )
    (comp (ref "R44")
      (value "3.3k")
      (footprint "J1-0603")
      (description "Resistor")
      (fields (field (name "PUBLISHER") "Altium Limited"))
      (libsource (lib "Miscellaneous Devices") (part "Res3"))
    )
    (comp (ref "R45")
      (value "3.3k")
      (footprint "J1-0603")
      (description "Resistor")
      (fields (field (name "PUBLISHER") "Altium Limited"))
      (libsource (lib "Miscellaneous Devices") (part "Res3"))
    )
    (comp (ref "R46")
      (value "330R")
      (footprint "J1-0603")
      (description "Resistor")
      (fields (field (name "PUBLISHER") "Altium Limited"))
      (libsource (lib "Miscellaneous Devices") (part "Res3"))
    )
    (comp (ref "R47")
      (value "330R")
      (footprint "J1-0603")
      (description "Resistor")
      (fields (field (name "PUBLISHER") "Altium Limited"))
      (libsource (lib "Miscellaneous Devices") (part "Res3"))
    )
    (comp (ref "R48")
      (value "330R")
      (footprint "J1-0603")
      (description "Resistor")
      (fields (field (name "PUBLISHER") "Altium Limited"))
      (libsource (lib "Miscellaneous Devices") (part "Res3"))
    )
    (comp (ref "R49")
      (value "330R")
      (footprint "J1-0603")
      (description "Resistor")
      (fields (field (name "PUBLISHER") "Altium Limited"))
      (libsource (lib "Miscellaneous Devices") (part "Res3"))
    )
    (comp (ref "R50")
      (value "330R")
      (footprint "J1-0603")
      (description "Resistor")
      (fields (field (name "PUBLISHER") "Altium Limited"))
      (libsource (lib "Miscellaneous Devices") (part "Res3"))
    )
    (comp (ref "R51")
      (value "330R")
      (footprint "J1-0603")
      (description "Resistor")
      (fields (field (name "PUBLISHER") "Altium Limited"))
      (libsource (lib "Miscellaneous Devices") (part "Res3"))
    )
    (comp (ref "R52")
      (value "330R")
      (footprint "J1-0603")
      (description "Resistor")
      (fields (field (name "PUBLISHER") "Altium Limited"))
      (libsource (lib "Miscellaneous Devices") (part "Res3"))
    )
    (comp (ref "R53")
      (value "330R")
      (footprint "J1-0603")
      (description "Resistor")
      (fields (field (name "PUBLISHER") "Altium Limited"))
      (libsource (lib "Miscellaneous Devices") (part "Res3"))
    )
    (comp (ref "R54")
      (value "330R")
      (footprint "J1-0603")
      (description "Resistor")
      (fields (field (name "PUBLISHER") "Altium Limited"))
      (libsource (lib "Miscellaneous Devices") (part "Res3"))
    )
    (comp (ref "R55")
      (value "330R")
      (footprint "J1-0603")
      (description "Resistor")
      (fields (field (name "PUBLISHER") "Altium Limited"))
      (libsource (lib "Miscellaneous Devices") (part "Res3"))
    )
    (comp (ref "R56")
      (value "330R")
      (footprint "J1-0603")
      (description "Resistor")
      (fields (field (name "PUBLISHER") "Altium Limited"))
      (libsource (lib "Miscellaneous Devices") (part "Res3"))
    )
    (comp (ref "R57")
      (value "330R")
      (footprint "J1-0603")
      (description "Resistor")
      (fields (field (name "PUBLISHER") "Altium Limited"))
      (libsource (lib "Miscellaneous Devices") (part "Res3"))
    )
    (comp (ref "R59")
      (value "3.3k")
      (footprint "J1-0603")
      (description "Resistor")
      (fields (field (name "PUBLISHER") "Altium Limited"))
      (libsource (lib "Miscellaneous Devices") (part "Res3"))
    )
    (comp (ref "R60")
      (value "3.3k")
      (footprint "J1-0603")
      (description "Resistor")
      (fields (field (name "PUBLISHER") "Altium Limited"))
      (libsource (lib "Miscellaneous Devices") (part "Res3"))
    )
    (comp (ref "R61")
      (value "3.3k")
      (footprint "J1-0603")
      (description "Resistor")
      (fields (field (name "PUBLISHER") "Altium Limited"))
      (libsource (lib "Miscellaneous Devices") (part "Res3"))
    )
    (comp (ref "R62")
      (value "3.3k")
      (footprint "J1-0603")
      (description "Resistor")
      (fields (field (name "PUBLISHER") "Altium Limited"))
      (libsource (lib "Miscellaneous Devices") (part "Res3"))
    )
    (comp (ref "R63")
      (value "3.3k")
      (footprint "J1-0603")
      (description "Resistor")
      (fields (field (name "PUBLISHER") "Altium Limited"))
      (libsource (lib "Miscellaneous Devices") (part "Res3"))
    )
    (comp (ref "R64")
      (value "3.3k")
      (footprint "J1-0603")
      (description "Resistor")
      (fields (field (name "PUBLISHER") "Altium Limited"))
      (libsource (lib "Miscellaneous Devices") (part "Res3"))
    )
    (comp (ref "R65")
      (value "3.3k")
      (footprint "J1-0603")
      (description "Resistor")
      (fields (field (name "PUBLISHER") "Altium Limited"))
      (libsource (lib "Miscellaneous Devices") (part "Res3"))
    )
    (comp (ref "R66")
      (value "3.3k")
      (footprint "J1-0603")
      (description "Resistor")
      (fields (field (name "PUBLISHER") "Altium Limited"))
      (libsource (lib "Miscellaneous Devices") (part "Res3"))
    )
    (comp (ref "R67")
      (value "3.3k")
      (footprint "J1-0603")
      (description "Resistor")
      (fields (field (name "PUBLISHER") "Altium Limited"))
      (libsource (lib "Miscellaneous Devices") (part "Res3"))
    )
    (comp (ref "R68")
      (value "3.3k")
      (footprint "J1-0603")
      (description "Resistor")
      (fields (field (name "PUBLISHER") "Altium Limited"))
      (libsource (lib "Miscellaneous Devices") (part "Res3"))
    )
    (comp (ref "R69")
      (value "3.3k")
      (footprint "J1-0603")
      (description "Resistor")
      (fields (field (name "PUBLISHER") "Altium Limited"))
      (libsource (lib "Miscellaneous Devices") (part "Res3"))
    )
    (comp (ref "R70")
      (value "3.3k")
      (footprint "J1-0603")
      (description "Resistor")
      (fields (field (name "PUBLISHER") "Altium Limited"))
      (libsource (lib "Miscellaneous Devices") (part "Res3"))
    )
    (comp (ref "R71")
      (value "3.3k")
      (footprint "J1-0603")
      (description "Resistor")
      (fields (field (name "PUBLISHER") "Altium Limited"))
      (libsource (lib "Miscellaneous Devices") (part "Res3"))
    )
    (comp (ref "R72")
      (value "3.3k")
      (footprint "J1-0603")
      (description "Resistor")
      (fields (field (name "PUBLISHER") "Altium Limited"))
      (libsource (lib "Miscellaneous Devices") (part "Res3"))
    )
    (comp (ref "R73")
      (value "3.3k")
      (footprint "J1-0603")
      (description "Resistor")
      (fields (field (name "PUBLISHER") "Altium Limited"))
      (libsource (lib "Miscellaneous Devices") (part "Res3"))
    )
    (comp (ref "R74")
      (value "3.3k")
      (footprint "J1-0603")
      (description "Resistor")
      (fields (field (name "PUBLISHER") "Altium Limited"))
      (libsource (lib "Miscellaneous Devices") (part "Res3"))
    )
    (comp (ref "R75")
      (value "3.3k")
      (footprint "J1-0603")
      (description "Resistor")
      (fields (field (name "PUBLISHER") "Altium Limited"))
      (libsource (lib "Miscellaneous Devices") (part "Res3"))
    )
    (comp (ref "R76")
      (value "3.3k")
      (footprint "J1-0603")
      (description "Resistor")
      (fields (field (name "PUBLISHER") "Altium Limited"))
      (libsource (lib "Miscellaneous Devices") (part "Res3"))
    )
    (comp (ref "R77")
      (value "3.3k")
      (footprint "J1-0603")
      (description "Resistor")
      (fields (field (name "PUBLISHER") "Altium Limited"))
      (libsource (lib "Miscellaneous Devices") (part "Res3"))
    )
    (comp (ref "R78")
      (value "3.3k")
      (footprint "J1-0603")
      (description "Resistor")
      (fields (field (name "PUBLISHER") "Altium Limited"))
      (libsource (lib "Miscellaneous Devices") (part "Res3"))
    )
    (comp (ref "R79")
      (value "3.3k")
      (footprint "J1-0603")
      (description "Resistor")
      (fields (field (name "PUBLISHER") "Altium Limited"))
      (libsource (lib "Miscellaneous Devices") (part "Res3"))
    )
    (comp (ref "R80")
      (value "3.3k")
      (footprint "J1-0603")
      (description "Resistor")
      (fields (field (name "PUBLISHER") "Altium Limited"))
      (libsource (lib "Miscellaneous Devices") (part "Res3"))
    )
    (comp (ref "R81")
      (value "3.3k")
      (footprint "J1-0603")
      (description "Resistor")
      (fields (field (name "PUBLISHER") "Altium Limited"))
      (libsource (lib "Miscellaneous Devices") (part "Res3"))
    )
    (comp (ref "R82")
      (value "3.3k")
      (footprint "J1-0603")
      (description "Resistor")
      (fields (field (name "PUBLISHER") "Altium Limited"))
      (libsource (lib "Miscellaneous Devices") (part "Res3"))
    )
    (comp (ref "R83")
      (value "330")
      (footprint "J1-0603")
      (description "Resistor")
      (fields (field (name "Comment") "330R") (field (name "PUBLISHER") "Altium Limited"))
      (libsource (lib "Miscellaneous Devices") (part "Res3"))
    )
    (comp (ref "R84")
      (value "330")
      (footprint "J1-0603")
      (description "Resistor")
      (fields (field (name "Comment") "330R") (field (name "PUBLISHER") "Altium Limited"))
      (libsource (lib "Miscellaneous Devices") (part "Res3"))
    )
    (comp (ref "R85")
      (value "330")
      (footprint "J1-0603")
      (description "Resistor")
      (fields (field (name "Comment") "330R") (field (name "PUBLISHER") "Altium Limited"))
      (libsource (lib "Miscellaneous Devices") (part "Res3"))
    )
    (comp (ref "R86")
      (value "330")
      (footprint "J1-0603")
      (description "Resistor")
      (fields (field (name "Comment") "330R") (field (name "PUBLISHER") "Altium Limited"))
      (libsource (lib "Miscellaneous Devices") (part "Res3"))
    )
    (comp (ref "R87")
      (value "1k")
      (footprint "J1-0603")
      (description "Resistor")
      (fields (field (name "PUBLISHER") "Altium Limited"))
      (libsource (lib "Miscellaneous Devices") (part "Res3"))
    )
    (comp (ref "R88")
      (value "1k")
      (footprint "J1-0603")
      (description "Resistor")
      (fields (field (name "PUBLISHER") "Altium Limited"))
      (libsource (lib "Miscellaneous Devices") (part "Res3"))
    )
    (comp (ref "R89")
      (value "1k")
      (footprint "J1-0603")
      (description "Resistor")
      (fields (field (name "PUBLISHER") "Altium Limited"))
      (libsource (lib "Miscellaneous Devices") (part "Res3"))
    )
    (comp (ref "R90")
      (value "1k")
      (footprint "J1-0603")
      (description "Resistor")
      (fields (field (name "PUBLISHER") "Altium Limited"))
      (libsource (lib "Miscellaneous Devices") (part "Res3"))
    )
    (comp (ref "R91")
      (value "330")
      (footprint "J1-0603")
      (description "Resistor")
      (fields (field (name "Comment") "330R") (field (name "PUBLISHER") "Altium Limited"))
      (libsource (lib "Miscellaneous Devices") (part "Res3"))
    )
    (comp (ref "R92")
      (value "330")
      (footprint "J1-0603")
      (description "Resistor")
      (fields (field (name "Comment") "330R") (field (name "PUBLISHER") "Altium Limited"))
      (libsource (lib "Miscellaneous Devices") (part "Res3"))
    )
    (comp (ref "R93")
      (value "330")
      (footprint "J1-0603")
      (description "Resistor")
      (fields (field (name "Comment") "330R") (field (name "PUBLISHER") "Altium Limited"))
      (libsource (lib "Miscellaneous Devices") (part "Res3"))
    )
    (comp (ref "R94")
      (value "330")
      (footprint "J1-0603")
      (description "Resistor")
      (fields (field (name "Comment") "330R") (field (name "PUBLISHER") "Altium Limited"))
      (libsource (lib "Miscellaneous Devices") (part "Res3"))
    )
    (comp (ref "R95")
      (value "330")
      (footprint "J1-0603")
      (description "Resistor")
      (fields (field (name "Comment") "330R") (field (name "PUBLISHER") "Altium Limited"))
      (libsource (lib "Miscellaneous Devices") (part "Res3"))
    )
    (comp (ref "R96")
      (value "330")
      (footprint "J1-0603")
      (description "Resistor")
      (fields (field (name "Comment") "330R") (field (name "PUBLISHER") "Altium Limited"))
      (libsource (lib "Miscellaneous Devices") (part "Res3"))
    )
    (comp (ref "R97")
      (value "330")
      (footprint "J1-0603")
      (description "Resistor")
      (fields (field (name "Comment") "330R") (field (name "PUBLISHER") "Altium Limited"))
      (libsource (lib "Miscellaneous Devices") (part "Res3"))
    )
    (comp (ref "R98")
      (value "330")
      (footprint "J1-0603")
      (description "Resistor")
      (fields (field (name "Comment") "330R") (field (name "PUBLISHER") "Altium Limited"))
      (libsource (lib "Miscellaneous Devices") (part "Res3"))
    )
    (comp (ref "R99")
      (value "1k")
      (footprint "J1-0603")
      (description "Resistor")
      (fields (field (name "PUBLISHER") "Altium Limited"))
      (libsource (lib "Miscellaneous Devices") (part "Res3"))
    )
    (comp (ref "R100")
      (value "1k")
      (footprint "J1-0603")
      (description "Resistor")
      (fields (field (name "PUBLISHER") "Altium Limited"))
      (libsource (lib "Miscellaneous Devices") (part "Res3"))
    )
    (comp (ref "R101")
      (value "1k")
      (footprint "J1-0603")
      (description "Resistor")
      (fields (field (name "PUBLISHER") "Altium Limited"))
      (libsource (lib "Miscellaneous Devices") (part "Res3"))
    )
    (comp (ref "R102")
      (value "1k")
      (footprint "J1-0603")
      (description "Resistor")
      (fields (field (name "PUBLISHER") "Altium Limited"))
      (libsource (lib "Miscellaneous Devices") (part "Res3"))
    )
    (comp (ref "R103")
      (value "1k")
      (footprint "J1-0603")
      (description "Resistor")
      (fields (field (name "PUBLISHER") "Altium Limited"))
      (libsource (lib "Miscellaneous Devices") (part "Res3"))
    )
    (comp (ref "R104")
      (value "1k")
      (footprint "J1-0603")
      (description "Resistor")
      (fields (field (name "PUBLISHER") "Altium Limited"))
      (libsource (lib "Miscellaneous Devices") (part "Res3"))
    )
    (comp (ref "R105")
      (value "1k")
      (footprint "J1-0603")
      (description "Resistor")
      (fields (field (name "PUBLISHER") "Altium Limited"))
      (libsource (lib "Miscellaneous Devices") (part "Res3"))
    )
    (comp (ref "R106")
      (value "1k")
      (footprint "J1-0603")
      (description "Resistor")
      (fields (field (name "PUBLISHER") "Altium Limited"))
      (libsource (lib "Miscellaneous Devices") (part "Res3"))
    )
    (comp (ref "R107")
      (value "180")
      (footprint "14-1210")
      (description "Resistor")
      (fields (field (name "Comment") "180R") (field (name "PUBLISHER") "Altium Limited"))
      (libsource (lib "Miscellaneous Devices") (part "Res3"))
    )
    (comp (ref "S1")
      (value "PVB4OA")
      (footprint "PVB4")
      (description "Tactile Switch, DPST; Thru-Hole; Vertical; Rating DC 12V, 50mA (max)")
      (fields (field (name "PUBLISHER") "Altium Limited"))
      (libsource (lib "IL Switch Push Button") (part "PVB4OA"))
    )
    (comp (ref "S2")
      (value "PVB4OA")
      (footprint "PVB4")
      (description "Tactile Switch, DPST; Thru-Hole; Vertical; Rating DC 12V, 50mA (max)")
      (fields (field (name "PUBLISHER") "Altium Limited"))
      (libsource (lib "IL Switch Push Button") (part "PVB4OA"))
    )
    (comp (ref "U1")
      (value "XC2S50-5PQG208C")
      (footprint "PQG208_N")
      (description "Spartan-II 2.5V FPGA, 140 User I/Os, 208-Pin PQFP, Standard Performance, Commercial Grade, Pb-Free")
      (fields (field (name "PUBLISHER") "Altium Limited"))
      (libsource (lib "Xilinx Spartan-II") (part "XC2S50-5PQG208C"))
    )
    (comp (ref "U2")
      (value "XC18V01SOG20C")
      (footprint "SOG20_N")
      (fields (field (name "PUBLISHER") "Altium Limited"))
      (libsource (lib "Xilinx XC18V00") (part "XC18V01SOG20C"))
    )
    (comp (ref "U3") (value "LT1764A") (footprint "LT1764A") (libsource (lib "Connectors") (part "LT1764A")))
    (comp (ref "U4") (value "TPS3823") (footprint "SOT23-5") (libsource (lib "Connectors") (part "TPS3823")))
    (comp (ref "U5") (value "LT1764A") (footprint "LT1764A") (libsource (lib "Connectors") (part "LT1764A")))
    (comp (ref "U6") (value "CB3") (footprint "CB3") (libsource (lib "Connectors") (part "CB3")))
    (comp (ref "U7") (value "uA9638C") (footprint "SO8_N") (libsource (lib "Connectors") (part "uA9638C")))
    (comp (ref "U8") (value "uA9638C") (footprint "SO8_N") (libsource (lib "Connectors") (part "uA9638C")))
    (comp (ref "U9") (value "uA9638C") (footprint "SO8_N") (libsource (lib "Connectors") (part "uA9638C")))
    (comp (ref "U10") (value "uA9638C") (footprint "SO8_N") (libsource (lib "Connectors") (part "uA9638C")))
    (comp (ref "U11") (value "uA9638C") (footprint "SO8_N") (libsource (lib "Connectors") (part "uA9638C")))
    (comp (ref "U12") (value "uA9638C") (footprint "SO8_N") (libsource (lib "Connectors") (part "uA9638C")))
    (comp (ref "U13") (value "SN7407DR") (footprint "SO14") (libsource (lib "Connectors") (part "SN7407DR")))
    (comp (ref "U14") (value "SN7407DR") (footprint "SO14") (libsource (lib "Connectors") (part "SN7407DR")))
    (comp (ref "U15")
      (value "TLP291-4")
      (footprint "TOSHIBA_11_11F1")
      (description "4-Pin Phototransistor Optocoupler")
      (fields (field (name "PUBLISHER") "Altium Limited"))
      (libsource (lib "Connectors") (part "TLP291-4"))
    )
    (comp (ref "U16")
      (value "TLP291-4")
      (footprint "TOSHIBA_11_11F1")
      (description "4-Pin Phototransistor Optocoupler")
      (fields (field (name "PUBLISHER") "Altium Limited"))
      (libsource (lib "Connectors") (part "TLP291-4"))
    )
    (comp (ref "U17")
      (value "TLP291-4")
      (footprint "TOSHIBA_11_11F1")
      (description "4-Pin Phototransistor Optocoupler")
      (fields (field (name "PUBLISHER") "Altium Limited"))
      (libsource (lib "Connectors") (part "TLP291-4"))
    )
    (comp (ref "U18") (value "CB3") (footprint "CB3") (libsource (lib "Connectors") (part "CB3")))
  )
  (nets
    (net (code "1") (name "/AD_N") (class "Default")
      (node (ref "J1") (pin "39") (pinfunction "39_39") (pintype "input"))
      (node (ref "R50") (pin "2") (pinfunction "2_2") (pintype "passive"))
      (node (ref "U10") (pin "7") (pinfunction "7_7") (pintype "output"))
    )
    (net (code "2") (name "/AD_P") (class "Default")
      (node (ref "J1") (pin "12") (pinfunction "12_12") (pintype "input"))
      (node (ref "R50") (pin "1") (pinfunction "1_1") (pintype "passive"))
      (node (ref "U10") (pin "8") (pinfunction "8_8") (pintype "output"))
    )
    (net (code "3") (name "/AP_N") (class "Default")
      (node (ref "J1") (pin "40") (pinfunction "40_40") (pintype "input"))
      (node (ref "R51") (pin "2") (pinfunction "2_2") (pintype "passive"))
      (node (ref "U10") (pin "5") (pinfunction "5_5") (pintype "output"))
    )
    (net (code "4") (name "/AP_P") (class "Default")
      (node (ref "J1") (pin "11") (pinfunction "11_11") (pintype "input"))
      (node (ref "R51") (pin "1") (pinfunction "1_1") (pintype "passive"))
      (node (ref "U10") (pin "6") (pinfunction "6_6") (pintype "output"))
    )
    (net (code "5") (name "/AUX_CLK1") (class "Default")
      (node (ref "U1") (pin "80") (pinfunction "GCK0_(366)_80") (pintype "input"))
      (node (ref "U6") (pin "3") (pinfunction "OUT_3") (pintype "output"))
    )
    (net (code "6") (name "/AUX_CLK2") (class "Default")
      (node (ref "U1") (pin "77") (pinfunction "GCK1_(365)_77") (pintype "input"))
      (node (ref "U18") (pin "3") (pinfunction "OUT_3") (pintype "output"))
    )
    (net (code "7") (name "/BD_N") (class "Default")
      (node (ref "J1") (pin "41") (pinfunction "41_41") (pintype "input"))
      (node (ref "R52") (pin "2") (pinfunction "2_2") (pintype "passive"))
      (node (ref "U11") (pin "7") (pinfunction "7_7") (pintype "output"))
    )
    (net (code "8") (name "/BD_P") (class "Default")
      (node (ref "J1") (pin "10") (pinfunction "10_10") (pintype "input"))
      (node (ref "R52") (pin "1") (pinfunction "1_1") (pintype "passive"))
      (node (ref "U11") (pin "8") (pinfunction "8_8") (pintype "output"))
    )
    (net (code "9") (name "/BP_N") (class "Default")
      (node (ref "J1") (pin "42") (pinfunction "42_42") (pintype "input"))
      (node (ref "R53") (pin "2") (pinfunction "2_2") (pintype "passive"))
      (node (ref "U11") (pin "5") (pinfunction "5_5") (pintype "output"))
    )
    (net (code "10") (name "/BP_P") (class "Default")
      (node (ref "J1") (pin "9") (pinfunction "9_9") (pintype "input"))
      (node (ref "R53") (pin "1") (pinfunction "1_1") (pintype "passive"))
      (node (ref "U11") (pin "6") (pinfunction "6_6") (pintype "output"))
    )
    (net (code "11") (name "/CD_N") (class "Default")
      (node (ref "J1") (pin "43") (pinfunction "43_43") (pintype "input"))
      (node (ref "R54") (pin "2") (pinfunction "2_2") (pintype "passive"))
      (node (ref "U12") (pin "7") (pinfunction "7_7") (pintype "output"))
    )
    (net (code "12") (name "/CD_P") (class "Default")
      (node (ref "J1") (pin "8") (pinfunction "8_8") (pintype "input"))
      (node (ref "R54") (pin "1") (pinfunction "1_1") (pintype "passive"))
      (node (ref "U12") (pin "8") (pinfunction "8_8") (pintype "output"))
    )
    (net (code "13") (name "/CP_N") (class "Default")
      (node (ref "J1") (pin "44") (pinfunction "44_44") (pintype "input"))
      (node (ref "R55") (pin "2") (pinfunction "2_2") (pintype "passive"))
      (node (ref "U12") (pin "5") (pinfunction "5_5") (pintype "output"))
    )
    (net (code "14") (name "/CP_P") (class "Default")
      (node (ref "J1") (pin "7") (pinfunction "7_7") (pintype "input"))
      (node (ref "R55") (pin "1") (pinfunction "1_1") (pintype "passive"))
      (node (ref "U12") (pin "6") (pinfunction "6_6") (pintype "output"))
    )
    (net (code "15") (name "/FPGA_AD") (class "Default")
      (node (ref "R75") (pin "2") (pinfunction "2_2") (pintype "passive"))
      (node (ref "U1") (pin "151") (pinfunction "I/O_(569)_151") (pintype "bidirectional"))
      (node (ref "U10") (pin "2") (pinfunction "2_2") (pintype "input"))
    )
    (net (code "16") (name "/FPGA_AP") (class "Default")
      (node (ref "R76") (pin "1") (pinfunction "1_1") (pintype "passive"))
      (node (ref "U1") (pin "149") (pinfunction "I/O_(563)_149") (pintype "bidirectional"))
      (node (ref "U10") (pin "3") (pinfunction "3_3") (pintype "input"))
    )
    (net (code "17") (name "/FPGA_BD") (class "Default")
      (node (ref "R61") (pin "1") (pinfunction "1_1") (pintype "passive"))
      (node (ref "U1") (pin "147") (pinfunction "I/O_(554)_147") (pintype "bidirectional"))
      (node (ref "U11") (pin "2") (pinfunction "2_2") (pintype "input"))
    )
    (net (code "18") (name "/FPGA_BP") (class "Default")
      (node (ref "R62") (pin "2") (pinfunction "2_2") (pintype "passive"))
      (node (ref "U1") (pin "142") (pinfunction "I/O_(D2)_(548)_142") (pintype "bidirectional"))
      (node (ref "U11") (pin "3") (pinfunction "3_3") (pintype "input"))
    )
    (net (code "19") (name "/FPGA_CD") (class "Default")
      (node (ref "R79") (pin "2") (pinfunction "2_2") (pintype "passive"))
      (node (ref "U1") (pin "140") (pinfunction "I/O_(539)_140") (pintype "bidirectional"))
      (node (ref "U12") (pin "2") (pinfunction "2_2") (pintype "input"))
    )
    (net (code "20") (name "/FPGA_CP") (class "Default")
      (node (ref "R80") (pin "1") (pinfunction "1_1") (pintype "passive"))
      (node (ref "U1") (pin "138") (pinfunction "I/O_(533)_138") (pintype "bidirectional"))
      (node (ref "U12") (pin "3") (pinfunction "3_3") (pintype "input"))
    )
    (net (code "21") (name "/FPGA_IN1") (class "Default")
      (node (ref "R90") (pin "2") (pinfunction "2_2") (pintype "passive"))
      (node (ref "U1") (pin "178") (pinfunction "I/O,_VREF_(54)_178") (pintype "bidirectional"))
      (node (ref "U15") (pin "15") (pinfunction "15_15") (pintype "passive"))
    )
    (net (code "22") (name "/FPGA_IN2") (class "Default")
      (node (ref "R89") (pin "2") (pinfunction "2_2") (pintype "passive"))
      (node (ref "U1") (pin "179") (pinfunction "I/O_(57)_179") (pintype "bidirectional"))
      (node (ref "U15") (pin "13") (pinfunction "13_13") (pintype "passive"))
    )
    (net (code "23") (name "/FPGA_IN3") (class "Default")
      (node (ref "R88") (pin "2") (pinfunction "2_2") (pintype "passive"))
      (node (ref "U1") (pin "180") (pinfunction "I/O_(63)_180") (pintype "bidirectional"))
      (node (ref "U15") (pin "11") (pinfunction "11_11") (pintype "passive"))
    )
    (net (code "24") (name "/FPGA_IN4") (class "Default")
      (node (ref "R87") (pin "2") (pinfunction "2_2") (pintype "passive"))
      (node (ref "U1") (pin "181") (pinfunction "I/O_(66)_181") (pintype "bidirectional"))
      (node (ref "U15") (pin "9") (pinfunction "9_9") (pintype "passive"))
    )
    (net (code "25") (name "/FPGA_IN5") (class "Default")
      (node (ref "R106") (pin "2") (pinfunction "2_2") (pintype "passive"))
      (node (ref "U1") (pin "173") (pinfunction "I/O_(39)_173") (pintype "bidirectional"))
      (node (ref "U16") (pin "15") (pinfunction "15_15") (pintype "passive"))
    )
    (net (code "26") (name "/FPGA_IN6") (class "Default")
      (node (ref "R105") (pin "2") (pinfunction "2_2") (pintype "passive"))
      (node (ref "U1") (pin "174") (pinfunction "I/O_(45)_174") (pintype "bidirectional"))
      (node (ref "U16") (pin "13") (pinfunction "13_13") (pintype "passive"))
    )
    (net (code "27") (name "/FPGA_IN7") (class "Default")
      (node (ref "R104") (pin "2") (pinfunction "2_2") (pintype "passive"))
      (node (ref "U1") (pin "175") (pinfunction "I/O_(48)_175") (pintype "bidirectional"))
      (node (ref "U16") (pin "11") (pinfunction "11_11") (pintype "passive"))
    )
    (net (code "28") (name "/FPGA_IN8") (class "Default")
      (node (ref "R103") (pin "2") (pinfunction "2_2") (pintype "passive"))
      (node (ref "U1") (pin "176") (pinfunction "I/O_(51)_176") (pintype "bidirectional"))
      (node (ref "U16") (pin "9") (pinfunction "9_9") (pintype "passive"))
    )
    (net (code "29") (name "/FPGA_IN9") (class "Default")
      (node (ref "R102") (pin "2") (pinfunction "2_2") (pintype "passive"))
      (node (ref "U1") (pin "166") (pinfunction "I/O_(27)_166") (pintype "bidirectional"))
      (node (ref "U17") (pin "15") (pinfunction "15_15") (pintype "passive"))
    )
    (net (code "30") (name "/FPGA_IN10") (class "Default")
      (node (ref "R101") (pin "2") (pinfunction "2_2") (pintype "passive"))
      (node (ref "U1") (pin "167") (pinfunction "I/O_(30)_167") (pintype "bidirectional"))
      (node (ref "U17") (pin "13") (pinfunction "13_13") (pintype "passive"))
    )
    (net (code "31") (name "/FPGA_IN11") (class "Default")
      (node (ref "R100") (pin "2") (pinfunction "2_2") (pintype "passive"))
      (node (ref "U1") (pin "168") (pinfunction "I/O_(33)_168") (pintype "bidirectional"))
      (node (ref "U17") (pin "11") (pinfunction "11_11") (pintype "passive"))
    )
    (net (code "32") (name "/FPGA_IN12") (class "Default")
      (node (ref "R99") (pin "2") (pinfunction "2_2") (pintype "passive"))
      (node (ref "U1") (pin "172") (pinfunction "I/O_(36)_172") (pintype "bidirectional"))
      (node (ref "U17") (pin "9") (pinfunction "9_9") (pintype "passive"))
    )
    (net (code "33") (name "/FPGA_OUT1") (class "Default")
      (node (ref "R63") (pin "1") (pinfunction "1_1") (pintype "passive"))
      (node (ref "U1") (pin "129") (pinfunction "I/O,_TRDY_(512)_129") (pintype "bidirectional"))
      (node (ref "U13") (pin "1") (pinfunction "1_1") (pintype "input"))
    )
    (net (code "34") (name "/FPGA_OUT2") (class "Default")
      (node (ref "R64") (pin "1") (pinfunction "1_1") (pintype "passive"))
      (node (ref "U1") (pin "126") (pinfunction "I/O_(D4)_(500)_126") (pintype "bidirectional"))
      (node (ref "U13") (pin "3") (pinfunction "3_3") (pintype "input"))
    )
    (net (code "35") (name "/FPGA_OUT3") (class "Default")
      (node (ref "R65") (pin "1") (pinfunction "1_1") (pintype "passive"))
      (node (ref "U1") (pin "123") (pinfunction "I/O_(494)_123") (pintype "bidirectional"))
      (node (ref "U13") (pin "5") (pinfunction "5_5") (pintype "input"))
    )
    (net (code "36") (name "/FPGA_OUT4") (class "Default")
      (node (ref "R66") (pin "1") (pinfunction "1_1") (pintype "passive"))
      (node (ref "U1") (pin "121") (pinfunction "I/O_(488)_121") (pintype "bidirectional"))
      (node (ref "U13") (pin "9") (pinfunction "9_9") (pintype "input"))
    )
    (net (code "37") (name "/FPGA_OUT5") (class "Default")
      (node (ref "R67") (pin "1") (pinfunction "1_1") (pintype "passive"))
      (node (ref "U1") (pin "119") (pinfunction "I/O_(D5)_(479)_119") (pintype "bidirectional"))
      (node (ref "U13") (pin "11") (pinfunction "11_11") (pintype "input"))
    )
    (net (code "38") (name "/FPGA_OUT6") (class "Default")
      (node (ref "R68") (pin "1") (pinfunction "1_1") (pintype "passive"))
      (node (ref "U1") (pin "115") (pinfunction "I/O_(D6)_(476)_115") (pintype "bidirectional"))
      (node (ref "U13") (pin "13") (pinfunction "13_13") (pintype "input"))
    )
    (net (code "39") (name "/FPGA_OUT7") (class "Default")
      (node (ref "R69") (pin "1") (pinfunction "1_1") (pintype "passive"))
      (node (ref "U1") (pin "113") (pinfunction "I/O_(470)_113") (pintype "bidirectional"))
      (node (ref "U14") (pin "1") (pinfunction "1_1") (pintype "input"))
    )
    (net (code "40") (name "/FPGA_OUT8") (class "Default")
      (node (ref "R70") (pin "1") (pinfunction "1_1") (pintype "passive"))
      (node (ref "U1") (pin "111") (pinfunction "I/O,_VREF_(461)_111") (pintype "bidirectional"))
      (node (ref "U14") (pin "3") (pinfunction "3_3") (pintype "input"))
    )
    (net (code "41") (name "/FPGA_OUT9") (class "Default")
      (node (ref "R71") (pin "1") (pinfunction "1_1") (pintype "passive"))
      (node (ref "U1") (pin "109") (pinfunction "I/O_(452)_109") (pintype "bidirectional"))
      (node (ref "U14") (pin "5") (pinfunction "5_5") (pintype "input"))
    )
    (net (code "42") (name "/FPGA_OUT10") (class "Default")
      (node (ref "R72") (pin "1") (pinfunction "1_1") (pintype "passive"))
      (node (ref "U1") (pin "102") (pinfunction "I/O_(436)_102") (pintype "bidirectional"))
      (node (ref "U14") (pin "9") (pinfunction "9_9") (pintype "input"))
    )
    (net (code "43") (name "/FPGA_OUT11") (class "Default")
      (node (ref "R73") (pin "1") (pinfunction "1_1") (pintype "passive"))
      (node (ref "U1") (pin "100") (pinfunction "I/O_(427)_100") (pintype "bidirectional"))
      (node (ref "U14") (pin "11") (pinfunction "11_11") (pintype "input"))
    )
    (net (code "44") (name "/FPGA_OUT12") (class "Default")
      (node (ref "R74") (pin "1") (pinfunction "1_1") (pintype "passive"))
      (node (ref "U1") (pin "98") (pinfunction "I/O,_VREF_(418)_98") (pintype "bidirectional"))
      (node (ref "U14") (pin "13") (pinfunction "13_13") (pintype "input"))
    )
    (net (code "45") (name "/FPGA_RESET") (class "Default")
      (node (ref "R12") (pin "1") (pinfunction "1_1") (pintype "passive"))
      (node (ref "U1") (pin "97") (pinfunction "I/O_(415)_97") (pintype "bidirectional"))
      (node (ref "U4") (pin "1") (pinfunction "~{RESET}_1") (pintype "output"))
    )
    (net (code "46") (name "/FPGA_XD") (class "Default")
      (node (ref "R81") (pin "1") (pinfunction "1_1") (pintype "passive"))
      (node (ref "U1") (pin "165") (pinfunction "I/O_(21)_165") (pintype "bidirectional"))
      (node (ref "U7") (pin "2") (pinfunction "2_2") (pintype "input"))
    )
    (net (code "47") (name "/FPGA_XP") (class "Default")
      (node (ref "R82") (pin "2") (pinfunction "2_2") (pintype "passive"))
      (node (ref "U1") (pin "164") (pinfunction "I/O,_VREF_(18)_164") (pintype "bidirectional"))
      (node (ref "U7") (pin "3") (pinfunction "3_3") (pintype "input"))
    )
    (net (code "48") (name "/FPGA_YD") (class "Default")
      (node (ref "R77") (pin "2") (pinfunction "2_2") (pintype "passive"))
      (node (ref "U1") (pin "163") (pinfunction "I/O_(15)_163") (pintype "bidirectional"))
      (node (ref "U8") (pin "2") (pinfunction "2_2") (pintype "input"))
    )
    (net (code "49") (name "/FPGA_YP") (class "Default")
      (node (ref "R78") (pin "1") (pinfunction "1_1") (pintype "passive"))
      (node (ref "U1") (pin "162") (pinfunction "I/O_(9)_162") (pintype "bidirectional"))
      (node (ref "U8") (pin "3") (pinfunction "3_3") (pintype "input"))
    )
    (net (code "50") (name "/FPGA_ZD") (class "Default")
      (node (ref "R59") (pin "1") (pinfunction "1_1") (pintype "passive"))
      (node (ref "U1") (pin "161") (pinfunction "I/O_(~{WRITE})_(3)_161") (pintype "bidirectional"))
      (node (ref "U9") (pin "2") (pinfunction "2_2") (pintype "input"))
    )
    (net (code "51") (name "/FPGA_ZP") (class "Default")
      (node (ref "R60") (pin "2") (pinfunction "2_2") (pintype "passive"))
      (node (ref "U1") (pin "160") (pinfunction "I/O_(~{CS})_(0)_160") (pintype "bidirectional"))
      (node (ref "U9") (pin "3") (pinfunction "3_3") (pintype "input"))
    )
    (net (code "52") (name "/IN1") (class "Default")
      (node (ref "J1") (pin "24") (pinfunction "24_24") (pintype "output"))
      (node (ref "R83") (pin "2") (pinfunction "2_2") (pintype "passive"))
    )
    (net (code "53") (name "/IN2") (class "Default")
      (node (ref "J1") (pin "27") (pinfunction "27_27") (pintype "output"))
      (node (ref "R84") (pin "2") (pinfunction "2_2") (pintype "passive"))
    )
    (net (code "54") (name "/IN3") (class "Default")
      (node (ref "J1") (pin "25") (pinfunction "25_25") (pintype "output"))
      (node (ref "R85") (pin "2") (pinfunction "2_2") (pintype "passive"))
    )
    (net (code "55") (name "/IN4") (class "Default")
      (node (ref "J1") (pin "26") (pinfunction "26_26") (pintype "output"))
      (node (ref "R86") (pin "2") (pinfunction "2_2") (pintype "passive"))
    )
    (net (code "56") (name "/IN5") (class "Default")
      (node (ref "J1") (pin "22") (pinfunction "22_22") (pintype "output"))
      (node (ref "R91") (pin "2") (pinfunction "2_2") (pintype "passive"))
    )
    (net (code "57") (name "/IN6") (class "Default")
      (node (ref "J1") (pin "29") (pinfunction "29_29") (pintype "output"))
      (node (ref "R92") (pin "2") (pinfunction "2_2") (pintype "passive"))
    )
    (net (code "58") (name "/IN7") (class "Default")
      (node (ref "J1") (pin "23") (pinfunction "23_23") (pintype "output"))
      (node (ref "R93") (pin "2") (pinfunction "2_2") (pintype "passive"))
    )
    (net (code "59") (name "/IN8") (class "Default")
      (node (ref "J1") (pin "28") (pinfunction "28_28") (pintype "output"))
      (node (ref "R94") (pin "2") (pinfunction "2_2") (pintype "passive"))
    )
    (net (code "60") (name "/IN9") (class "Default")
      (node (ref "J1") (pin "20") (pinfunction "20_20") (pintype "output"))
      (node (ref "R95") (pin "2") (pinfunction "2_2") (pintype "passive"))
    )
    (net (code "61") (name "/IN10") (class "Default")
      (node (ref "J1") (pin "31") (pinfunction "31_31") (pintype "output"))
      (node (ref "R96") (pin "2") (pinfunction "2_2") (pintype "passive"))
    )
    (net (code "62") (name "/IN11") (class "Default")
      (node (ref "J1") (pin "21") (pinfunction "21_21") (pintype "output"))
      (node (ref "R97") (pin "2") (pinfunction "2_2") (pintype "passive"))
    )
    (net (code "63") (name "/IN12") (class "Default")
      (node (ref "J1") (pin "30") (pinfunction "30_30") (pintype "output"))
      (node (ref "R98") (pin "2") (pinfunction "2_2") (pintype "passive"))
    )
    (net (code "64") (name "/LED1") (class "Default")
      (node (ref "Q2") (pin "1") (pinfunction "B_1") (pintype "passive"))
      (node (ref "U1") (pin "86") (pinfunction "I/O_(385)_86") (pintype "bidirectional"))
    )
    (net (code "65") (name "/LED2") (class "Default")
      (node (ref "Q3") (pin "1") (pinfunction "B_1") (pintype "passive"))
      (node (ref "U1") (pin "87") (pinfunction "I/O_(388)_87") (pintype "bidirectional"))
    )
    (net (code "66") (name "/LED3") (class "Default")
      (node (ref "Q4") (pin "1") (pinfunction "B_1") (pintype "passive"))
      (node (ref "U1") (pin "88") (pinfunction "I/O_(391)_88") (pintype "bidirectional"))
    )
    (net (code "67") (name "/LED4") (class "Default")
      (node (ref "Q5") (pin "1") (pinfunction "B_1") (pintype "passive"))
      (node (ref "U1") (pin "89") (pinfunction "I/O_(397)_89") (pintype "bidirectional"))
    )
    (net (code "68") (name "/LED5") (class "Default")
      (node (ref "Q6") (pin "1") (pinfunction "B_1") (pintype "passive"))
      (node (ref "U1") (pin "90") (pinfunction "I/O_(400)_90") (pintype "bidirectional"))
    )
    (net (code "69") (name "/LED6") (class "Default")
      (node (ref "Q7") (pin "1") (pinfunction "B_1") (pintype "passive"))
      (node (ref "U1") (pin "94") (pinfunction "I/O_(403)_94") (pintype "bidirectional"))
    )
    (net (code "70") (name "/LED7") (class "Default")
      (node (ref "Q8") (pin "1") (pinfunction "B_1") (pintype "passive"))
      (node (ref "U1") (pin "95") (pinfunction "I/O_(406)_95") (pintype "bidirectional"))
    )
    (net (code "71") (name "/LED8") (class "Default")
      (node (ref "Q9") (pin "1") (pinfunction "B_1") (pintype "passive"))
      (node (ref "U1") (pin "96") (pinfunction "I/O_(409)_96") (pintype "bidirectional"))
    )
    (net (code "72") (name "/OUT1") (class "Default")
      (node (ref "J1") (pin "47") (pinfunction "47_47") (pintype "input"))
      (node (ref "R22") (pin "1") (pinfunction "1_1") (pintype "passive"))
      (node (ref "R34") (pin "2") (pinfunction "2_2") (pintype "passive"))
      (node (ref "U13") (pin "2") (pinfunction "2_2") (pintype "output"))
    )
    (net (code "73") (name "/OUT2") (class "Default")
      (node (ref "J1") (pin "4") (pinfunction "4_4") (pintype "input"))
      (node (ref "R23") (pin "1") (pinfunction "1_1") (pintype "passive"))
      (node (ref "R35") (pin "2") (pinfunction "2_2") (pintype "passive"))
      (node (ref "U13") (pin "4") (pinfunction "4_4") (pintype "output"))
    )
    (net (code "74") (name "/OUT3") (class "Default")
      (node (ref "J1") (pin "46") (pinfunction "46_46") (pintype "input"))
      (node (ref "R24") (pin "1") (pinfunction "1_1") (pintype "passive"))
      (node (ref "R36") (pin "2") (pinfunction "2_2") (pintype "passive"))
      (node (ref "U13") (pin "6") (pinfunction "6_6") (pintype "output"))
    )
    (net (code "75") (name "/OUT4") (class "Default")
      (node (ref "J1") (pin "6") (pinfunction "6_6") (pintype "input"))
      (node (ref "R25") (pin "1") (pinfunction "1_1") (pintype "passive"))
      (node (ref "R37") (pin "2") (pinfunction "2_2") (pintype "passive"))
      (node (ref "U13") (pin "8") (pinfunction "8_8") (pintype "output"))
    )
    (net (code "76") (name "/OUT5") (class "Default")
      (node (ref "J1") (pin "45") (pinfunction "45_45") (pintype "input"))
      (node (ref "R26") (pin "1") (pinfunction "1_1") (pintype "passive"))
      (node (ref "R38") (pin "2") (pinfunction "2_2") (pintype "passive"))
      (node (ref "U13") (pin "10") (pinfunction "10_10") (pintype "output"))
    )
    (net (code "77") (name "/OUT6") (class "Default")
      (node (ref "J1") (pin "5") (pinfunction "5_5") (pintype "input"))
      (node (ref "R27") (pin "1") (pinfunction "1_1") (pintype "passive"))
      (node (ref "R39") (pin "2") (pinfunction "2_2") (pintype "passive"))
      (node (ref "U13") (pin "12") (pinfunction "12_12") (pintype "output"))
    )
    (net (code "78") (name "/OUT7") (class "Default")
      (node (ref "J1") (pin "50") (pinfunction "50_50") (pintype "input"))
      (node (ref "R28") (pin "1") (pinfunction "1_1") (pintype "passive"))
      (node (ref "R40") (pin "2") (pinfunction "2_2") (pintype "passive"))
      (node (ref "U14") (pin "2") (pinfunction "2_2") (pintype "output"))
    )
    (net (code "79") (name "/OUT8") (class "Default")
      (node (ref "J1") (pin "1") (pinfunction "1_1") (pintype "input"))
      (node (ref "R29") (pin "1") (pinfunction "1_1") (pintype "passive"))
      (node (ref "R41") (pin "2") (pinfunction "2_2") (pintype "passive"))
      (node (ref "U14") (pin "4") (pinfunction "4_4") (pintype "output"))
    )
    (net (code "80") (name "/OUT9") (class "Default")
      (node (ref "J1") (pin "49") (pinfunction "49_49") (pintype "input"))
      (node (ref "R30") (pin "1") (pinfunction "1_1") (pintype "passive"))
      (node (ref "R42") (pin "2") (pinfunction "2_2") (pintype "passive"))
      (node (ref "U14") (pin "6") (pinfunction "6_6") (pintype "output"))
    )
    (net (code "81") (name "/OUT10") (class "Default")
      (node (ref "J1") (pin "3") (pinfunction "3_3") (pintype "input"))
      (node (ref "R31") (pin "1") (pinfunction "1_1") (pintype "passive"))
      (node (ref "R43") (pin "2") (pinfunction "2_2") (pintype "passive"))
      (node (ref "U14") (pin "8") (pinfunction "8_8") (pintype "output"))
    )
    (net (code "82") (name "/OUT11") (class "Default")
      (node (ref "J1") (pin "48") (pinfunction "48_48") (pintype "input"))
      (node (ref "R32") (pin "1") (pinfunction "1_1") (pintype "passive"))
      (node (ref "R44") (pin "2") (pinfunction "2_2") (pintype "passive"))
      (node (ref "U14") (pin "10") (pinfunction "10_10") (pintype "output"))
    )
    (net (code "83") (name "/OUT12") (class "Default")
      (node (ref "J1") (pin "2") (pinfunction "2_2") (pintype "input"))
      (node (ref "R33") (pin "1") (pinfunction "1_1") (pintype "passive"))
      (node (ref "R45") (pin "2") (pinfunction "2_2") (pintype "passive"))
      (node (ref "U14") (pin "12") (pinfunction "12_12") (pintype "output"))
    )
    (net (code "84") (name "/PCI_AD0") (class "Default")
      (node (ref "P1") (pin "A58") (pinfunction "AD[00]_A58") (pintype "bidirectional"))
      (node (ref "U1") (pin "67") (pinfunction "I/O_(329)_67") (pintype "bidirectional"))
    )
    (net (code "85") (name "/PCI_AD1") (class "Default")
      (node (ref "P1") (pin "B58") (pinfunction "AD[01]_B58") (pintype "bidirectional"))
      (node (ref "U1") (pin "63") (pinfunction "I/O_(326)_63") (pintype "bidirectional"))
    )
    (net (code "86") (name "/PCI_AD2") (class "Default")
      (node (ref "P1") (pin "A57") (pinfunction "AD[02]_A57") (pintype "bidirectional"))
      (node (ref "U1") (pin "62") (pinfunction "I/O_(323)_62") (pintype "bidirectional"))
    )
    (net (code "87") (name "/PCI_AD3") (class "Default")
      (node (ref "P1") (pin "B56") (pinfunction "AD[03]_B56") (pintype "bidirectional"))
      (node (ref "U1") (pin "61") (pinfunction "I/O_(320)_61") (pintype "bidirectional"))
    )
    (net (code "88") (name "/PCI_AD4") (class "Default")
      (node (ref "P1") (pin "A55") (pinfunction "AD[04]_A55") (pintype "bidirectional"))
      (node (ref "U1") (pin "59") (pinfunction "I/O,_VREF_(311)_59") (pintype "bidirectional"))
    )
    (net (code "89") (name "/PCI_AD5") (class "Default")
      (node (ref "P1") (pin "B55") (pinfunction "AD[05]_B55") (pintype "bidirectional"))
      (node (ref "U1") (pin "58") (pinfunction "I/O_(308)_58") (pintype "bidirectional"))
    )
    (net (code "90") (name "/PCI_AD6") (class "Default")
      (node (ref "P1") (pin "A54") (pinfunction "AD[06]_A54") (pintype "bidirectional"))
      (node (ref "U1") (pin "57") (pinfunction "I/O_(302)_57") (pintype "bidirectional"))
    )
    (net (code "91") (name "/PCI_AD7") (class "Default")
      (node (ref "P1") (pin "B53") (pinfunction "AD[07]_B53") (pintype "bidirectional"))
      (node (ref "U1") (pin "49") (pinfunction "I/O_(287)_49") (pintype "bidirectional"))
    )
    (net (code "92") (name "/PCI_AD8") (class "Default")
      (node (ref "P1") (pin "B52") (pinfunction "AD[08]_B52") (pintype "bidirectional"))
      (node (ref "U1") (pin "47") (pinfunction "I/O_(278)_47") (pintype "bidirectional"))
    )
    (net (code "93") (name "/PCI_AD9") (class "Default")
      (node (ref "P1") (pin "A49") (pinfunction "AD[09]_A49") (pintype "bidirectional"))
      (node (ref "U1") (pin "46") (pinfunction "I/O_(272)_46") (pintype "bidirectional"))
    )
    (net (code "94") (name "/PCI_AD10") (class "Default")
      (node (ref "P1") (pin "B48") (pinfunction "AD[10]_B48") (pintype "bidirectional"))
      (node (ref "U1") (pin "45") (pinfunction "I/O,_VREF_(269)_45") (pintype "bidirectional"))
    )
    (net (code "95") (name "/PCI_AD11") (class "Default")
      (node (ref "P1") (pin "A47") (pinfunction "AD[11]_A47") (pintype "bidirectional"))
      (node (ref "U1") (pin "43") (pinfunction "I/O_(260)_43") (pintype "bidirectional"))
    )
    (net (code "96") (name "/PCI_AD12") (class "Default")
      (node (ref "P1") (pin "B47") (pinfunction "AD[12]_B47") (pintype "bidirectional"))
      (node (ref "U1") (pin "42") (pinfunction "I/O_(257)_42") (pintype "bidirectional"))
    )
    (net (code "97") (name "/PCI_AD13") (class "Default")
      (node (ref "P1") (pin "A46") (pinfunction "AD[13]_A46") (pintype "bidirectional"))
      (node (ref "U1") (pin "41") (pinfunction "I/O_(254)_41") (pintype "bidirectional"))
    )
    (net (code "98") (name "/PCI_AD14") (class "Default")
      (node (ref "P1") (pin "B45") (pinfunction "AD[14]_B45") (pintype "bidirectional"))
      (node (ref "U1") (pin "37") (pinfunction "I/O_(251)_37") (pintype "bidirectional"))
    )
    (net (code "99") (name "/PCI_AD15") (class "Default")
      (node (ref "P1") (pin "A44") (pinfunction "AD[15]_A44") (pintype "bidirectional"))
      (node (ref "U1") (pin "36") (pinfunction "I/O_(248)_36") (pintype "bidirectional"))
    )
    (net (code "100") (name "/PCI_AD16") (class "Default")
      (node (ref "P1") (pin "A32") (pinfunction "AD[16]_A32") (pintype "bidirectional"))
      (node (ref "U1") (pin "21") (pinfunction "I/O_(203)_21") (pintype "bidirectional"))
    )
    (net (code "101") (name "/PCI_AD17") (class "Default")
      (node (ref "P1") (pin "B32") (pinfunction "AD[17]_B32") (pintype "bidirectional"))
      (node (ref "U1") (pin "20") (pinfunction "I/O,_VREF_(200)_20") (pintype "bidirectional"))
    )
    (net (code "102") (name "/PCI_AD18") (class "Default")
      (node (ref "P1") (pin "A31") (pinfunction "AD[18]_A31") (pintype "bidirectional"))
      (node (ref "U1") (pin "18") (pinfunction "I/O_(197)_18") (pintype "bidirectional"))
    )
    (net (code "103") (name "/PCI_AD19") (class "Default")
      (node (ref "P1") (pin "B30") (pinfunction "AD[19]_B30") (pintype "bidirectional"))
      (node (ref "U1") (pin "17") (pinfunction "I/O_(194)_17") (pintype "bidirectional"))
    )
    (net (code "104") (name "/PCI_AD20") (class "Default")
      (node (ref "P1") (pin "A29") (pinfunction "AD[20]_A29") (pintype "bidirectional"))
      (node (ref "U1") (pin "16") (pinfunction "I/O_(191)_16") (pintype "bidirectional"))
    )
    (net (code "105") (name "/PCI_AD21") (class "Default")
      (node (ref "P1") (pin "B29") (pinfunction "AD[21]_B29") (pintype "bidirectional"))
      (node (ref "U1") (pin "15") (pinfunction "I/O_(185)_15") (pintype "bidirectional"))
    )
    (net (code "106") (name "/PCI_AD22") (class "Default")
      (node (ref "P1") (pin "A28") (pinfunction "AD[22]_A28") (pintype "bidirectional"))
      (node (ref "U1") (pin "14") (pinfunction "I/O_(182)_14") (pintype "bidirectional"))
    )
    (net (code "107") (name "/PCI_AD23") (class "Default")
      (node (ref "P1") (pin "B27") (pinfunction "AD[23]_B27") (pintype "bidirectional"))
      (node (ref "U1") (pin "10") (pinfunction "I/O_(179)_10") (pintype "bidirectional"))
    )
    (net (code "108") (name "/PCI_AD24") (class "Default")
      (node (ref "P1") (pin "A25") (pinfunction "AD[24]_A25") (pintype "bidirectional"))
      (node (ref "U1") (pin "6") (pinfunction "I/O,_VREF_(164)_6") (pintype "bidirectional"))
    )
    (net (code "109") (name "/PCI_AD25") (class "Default")
      (node (ref "P1") (pin "B24") (pinfunction "AD[25]_B24") (pintype "bidirectional"))
      (node (ref "U1") (pin "5") (pinfunction "I/O_(161)_5") (pintype "bidirectional"))
    )
    (net (code "110") (name "/PCI_AD26") (class "Default")
      (node (ref "P1") (pin "A23") (pinfunction "AD[26]_A23") (pintype "bidirectional"))
      (node (ref "U1") (pin "4") (pinfunction "I/O_(155)_4") (pintype "bidirectional"))
    )
    (net (code "111") (name "/PCI_AD27") (class "Default")
      (node (ref "P1") (pin "B23") (pinfunction "AD[27]_B23") (pintype "bidirectional"))
      (node (ref "U1") (pin "3") (pinfunction "I/O_(149)_3") (pintype "bidirectional"))
    )
    (net (code "112") (name "/PCI_AD28") (class "Default")
      (node (ref "P1") (pin "A22") (pinfunction "AD[28]_A22") (pintype "bidirectional"))
      (node (ref "U1") (pin "206") (pinfunction "I/O_(140)_206") (pintype "bidirectional"))
    )
    (net (code "113") (name "/PCI_AD29") (class "Default")
      (node (ref "P1") (pin "B21") (pinfunction "AD[29]_B21") (pintype "bidirectional"))
      (node (ref "U1") (pin "205") (pinfunction "I/O_(134)_205") (pintype "bidirectional"))
    )
    (net (code "114") (name "/PCI_AD30") (class "Default")
      (node (ref "P1") (pin "A20") (pinfunction "AD[30]_A20") (pintype "bidirectional"))
      (node (ref "U1") (pin "204") (pinfunction "I/O_(128)_204") (pintype "bidirectional"))
    )
    (net (code "115") (name "/PCI_AD31") (class "Default")
      (node (ref "P1") (pin "B20") (pinfunction "AD[31]_B20") (pintype "bidirectional"))
      (node (ref "U1") (pin "203") (pinfunction "I/O,_VREF_(125)_203") (pintype "bidirectional"))
    )
    (net (code "116") (name "/PCI_CBE0") (class "Default")
      (node (ref "P1") (pin "A52") (pinfunction "C/BE[0]#_A52") (pintype "bidirectional"))
      (node (ref "U1") (pin "48") (pinfunction "I/O_(284)_48") (pintype "bidirectional"))
    )
    (net (code "117") (name "/PCI_CBE1") (class "Default")
      (node (ref "P1") (pin "B44") (pinfunction "C/BE[1]#_B44") (pintype "bidirectional"))
      (node (ref "U1") (pin "35") (pinfunction "I/O_(242)_35") (pintype "bidirectional"))
    )
    (net (code "118") (name "/PCI_CBE2") (class "Default")
      (node (ref "P1") (pin "B33") (pinfunction "C/BE[2]#_B33") (pintype "bidirectional"))
      (node (ref "U1") (pin "22") (pinfunction "I/O_(209)_22") (pintype "bidirectional"))
    )
    (net (code "119") (name "/PCI_CBE3") (class "Default")
      (node (ref "P1") (pin "B26") (pinfunction "C/BE[3]#_B26") (pintype "bidirectional"))
      (node (ref "U1") (pin "8") (pinfunction "I/O_(173)_8") (pintype "bidirectional"))
    )
    (net (code "120") (name "/PCI_CLK") (class "Default")
      (node (ref "P1") (pin "B16") (pinfunction "CLK_B16") (pintype "output"))
      (node (ref "U1") (pin "185") (pinfunction "GCK3_(73)_185") (pintype "input"))
    )
    (net (code "121") (name "/PCI_DEVSEL") (class "Default")
      (node (ref "P1") (pin "B37") (pinfunction "DEVSEL#_B37") (pintype "bidirectional"))
      (node (ref "U1") (pin "29") (pinfunction "I/O_(224)_29") (pintype "bidirectional"))
    )
    (net (code "122") (name "/PCI_FRAME") (class "Default")
      (node (ref "P1") (pin "A34") (pinfunction "FRAME#_A34") (pintype "bidirectional"))
      (node (ref "U1") (pin "23") (pinfunction "I/O_(212)_23") (pintype "bidirectional"))
    )
    (net (code "123") (name "/PCI_GNT") (class "Default")
      (node (ref "P1") (pin "A17") (pinfunction "GNT#_A17") (pintype "output"))
      (node (ref "U1") (pin "200") (pinfunction "I/O_(113)_200") (pintype "bidirectional"))
    )
    (net (code "124") (name "/PCI_IDSEL") (class "Default")
      (node (ref "P1") (pin "A26") (pinfunction "IDSEL_A26") (pintype "output"))
      (node (ref "U1") (pin "9") (pinfunction "I/O_(176)_9") (pintype "bidirectional"))
    )
    (net (code "125") (name "/PCI_INTA") (class "Default")
      (node (ref "P1") (pin "A6") (pinfunction "INTA#_A6") (pintype "open_collector"))
      (node (ref "U1") (pin "195") (pinfunction "I/O_(107)_195") (pintype "bidirectional"))
    )
    (net (code "126") (name "/PCI_IRDY") (class "Default")
      (node (ref "P1") (pin "B35") (pinfunction "IRDY#_B35") (pintype "bidirectional"))
      (node (ref "U1") (pin "24") (pinfunction "I/O,_IRDY_(215)_24") (pintype "bidirectional"))
    )
    (net (code "127") (name "/PCI_PAR") (class "Default")
      (node (ref "P1") (pin "A43") (pinfunction "PAR_A43") (pintype "bidirectional"))
      (node (ref "U1") (pin "34") (pinfunction "I/O_(239)_34") (pintype "bidirectional"))
    )
    (net (code "128") (name "/PCI_PERR") (class "Default")
      (node (ref "P1") (pin "B40") (pinfunction "PERR#_B40") (pintype "input"))
      (node (ref "U1") (pin "31") (pinfunction "I/O,_VREF_(233)_31") (pintype "bidirectional"))
    )
    (net (code "129") (name "/PCI_REQ") (class "Default")
      (node (ref "P1") (pin "B18") (pinfunction "REQ#_B18") (pintype "input"))
      (node (ref "U1") (pin "201") (pinfunction "I/O_(116)_201") (pintype "bidirectional"))
    )
    (net (code "130") (name "/PCI_RST") (class "Default")
      (node (ref "P1") (pin "A15") (pinfunction "RST#_A15") (pintype "output"))
      (node (ref "U1") (pin "199") (pinfunction "I/O_(110)_199") (pintype "bidirectional"))
    )
    (net (code "131") (name "/PCI_SERR") (class "Default")
      (node (ref "P1") (pin "B42") (pinfunction "SERR#_B42") (pintype "open_collector"))
      (node (ref "U1") (pin "33") (pinfunction "I/O_(236)_33") (pintype "bidirectional"))
    )
    (net (code "132") (name "/PCI_STOP") (class "Default")
      (node (ref "P1") (pin "A38") (pinfunction "STOP#_A38") (pintype "bidirectional"))
      (node (ref "U1") (pin "30") (pinfunction "I/O_(230)_30") (pintype "bidirectional"))
    )
    (net (code "133") (name "/PCI_TRDY") (class "Default")
      (node (ref "P1") (pin "A36") (pinfunction "TRDY#_A36") (pintype "bidirectional"))
      (node (ref "U1") (pin "27") (pinfunction "I/O,_TRDY_(218)_27") (pintype "bidirectional"))
    )
    (net (code "134") (name "/XD_N") (class "Default")
      (node (ref "J1") (pin "19") (pinfunction "19_19") (pintype "input"))
      (node (ref "R56") (pin "2") (pinfunction "2_2") (pintype "passive"))
      (node (ref "U7") (pin "7") (pinfunction "7_7") (pintype "output"))
    )
    (net (code "135") (name "/XD_P") (class "Default")
      (node (ref "J1") (pin "32") (pinfunction "32_32") (pintype "input"))
      (node (ref "R56") (pin "1") (pinfunction "1_1") (pintype "passive"))
      (node (ref "U7") (pin "8") (pinfunction "8_8") (pintype "output"))
    )
    (net (code "136") (name "/XP_N") (class "Default")
      (node (ref "J1") (pin "18") (pinfunction "18_18") (pintype "input"))
      (node (ref "R57") (pin "2") (pinfunction "2_2") (pintype "passive"))
      (node (ref "U7") (pin "5") (pinfunction "5_5") (pintype "output"))
    )
    (net (code "137") (name "/XP_P") (class "Default")
      (node (ref "J1") (pin "33") (pinfunction "33_33") (pintype "input"))
      (node (ref "R57") (pin "1") (pinfunction "1_1") (pintype "passive"))
      (node (ref "U7") (pin "6") (pinfunction "6_6") (pintype "output"))
    )
    (net (code "138") (name "/YD_N") (class "Default")
      (node (ref "J1") (pin "17") (pinfunction "17_17") (pintype "input"))
      (node (ref "R46") (pin "2") (pinfunction "2_2") (pintype "passive"))
      (node (ref "U8") (pin "7") (pinfunction "7_7") (pintype "output"))
    )
    (net (code "139") (name "/YD_P") (class "Default")
      (node (ref "J1") (pin "34") (pinfunction "34_34") (pintype "input"))
      (node (ref "R46") (pin "1") (pinfunction "1_1") (pintype "passive"))
      (node (ref "U8") (pin "8") (pinfunction "8_8") (pintype "output"))
    )
    (net (code "140") (name "/YP_N") (class "Default")
      (node (ref "J1") (pin "16") (pinfunction "16_16") (pintype "input"))
      (node (ref "R47") (pin "2") (pinfunction "2_2") (pintype "passive"))
      (node (ref "U8") (pin "5") (pinfunction "5_5") (pintype "output"))
    )
    (net (code "141") (name "/YP_P") (class "Default")
      (node (ref "J1") (pin "35") (pinfunction "35_35") (pintype "input"))
      (node (ref "R47") (pin "1") (pinfunction "1_1") (pintype "passive"))
      (node (ref "U8") (pin "6") (pinfunction "6_6") (pintype "output"))
    )
    (net (code "142") (name "/ZD_N") (class "Default")
      (node (ref "J1") (pin "15") (pinfunction "15_15") (pintype "input"))
      (node (ref "R48") (pin "2") (pinfunction "2_2") (pintype "passive"))
      (node (ref "U9") (pin "7") (pinfunction "7_7") (pintype "output"))
    )
    (net (code "143") (name "/ZD_P") (class "Default")
      (node (ref "J1") (pin "36") (pinfunction "36_36") (pintype "input"))
      (node (ref "R48") (pin "1") (pinfunction "1_1") (pintype "passive"))
      (node (ref "U9") (pin "8") (pinfunction "8_8") (pintype "output"))
    )
    (net (code "144") (name "/ZP_N") (class "Default")
      (node (ref "J1") (pin "14") (pinfunction "14_14") (pintype "input"))
      (node (ref "R49") (pin "2") (pinfunction "2_2") (pintype "passive"))
      (node (ref "U9") (pin "5") (pinfunction "5_5") (pintype "output"))
    )
    (net (code "145") (name "/ZP_P") (class "Default")
      (node (ref "J1") (pin "37") (pinfunction "37_37") (pintype "input"))
      (node (ref "R49") (pin "1") (pinfunction "1_1") (pintype "passive"))
      (node (ref "U9") (pin "6") (pinfunction "6_6") (pintype "output"))
    )
    (net (code "146") (name "2V5") (class "Default")
      (node (ref "Cb118") (pin "-") (pinfunction "-_-") (pintype "passive"))
      (node (ref "Cb128") (pin "-") (pinfunction "-_-") (pintype "passive"))
      (node (ref "Cb13") (pin "-") (pinfunction "-_-") (pintype "passive"))
      (node (ref "Cb143") (pin "-") (pinfunction "-_-") (pintype "passive"))
      (node (ref "Cb171") (pin "-") (pinfunction "-_-") (pintype "passive"))
      (node (ref "Cb186") (pin "-") (pinfunction "-_-") (pintype "passive"))
      (node (ref "Cb196") (pin "-") (pinfunction "-_-") (pintype "passive"))
      (node (ref "Cb28") (pin "-") (pinfunction "-_-") (pintype "passive"))
      (node (ref "Cb38") (pin "-") (pinfunction "-_-") (pintype "passive"))
      (node (ref "Cb66") (pin "-") (pinfunction "-_-") (pintype "passive"))
      (node (ref "Cb76") (pin "-") (pinfunction "-_-") (pintype "passive"))
      (node (ref "Cb91") (pin "-") (pinfunction "-_-") (pintype "passive"))
      (node (ref "CbJ") (pin "-") (pinfunction "-_-") (pintype "passive"))
      (node (ref "CbU4") (pin "-") (pinfunction "-_-") (pintype "passive"))
      (node (ref "Cp4") (pin "-") (pinfunction "-_-") (pintype "passive"))
      (node (ref "JTAG") (pin "4") (pinfunction "VCC_4") (pintype "power_in"))
      (node (ref "R11") (pin "2") (pinfunction "2_2") (pintype "passive"))
      (node (ref "R12") (pin "2") (pinfunction "2_2") (pintype "passive"))
      (node (ref "R9") (pin "1") (pinfunction "1_1") (pintype "passive"))
      (node (ref "U1") (pin "118") (pinfunction "VCCINT_118") (pintype "power_in"))
      (node (ref "U1") (pin "128") (pinfunction "VCCINT_128") (pintype "power_in"))
      (node (ref "U1") (pin "13") (pinfunction "VCCINT_13") (pintype "power_in"))
      (node (ref "U1") (pin "143") (pinfunction "VCCINT_143") (pintype "power_in"))
      (node (ref "U1") (pin "171") (pinfunction "VCCINT_171") (pintype "power_in"))
      (node (ref "U1") (pin "186") (pinfunction "VCCINT_186") (pintype "power_in"))
      (node (ref "U1") (pin "196") (pinfunction "VCCINT_196") (pintype "power_in"))
      (node (ref "U1") (pin "28") (pinfunction "VCCINT_28") (pintype "power_in"))
      (node (ref "U1") (pin "38") (pinfunction "VCCINT_38") (pintype "power_in"))
      (node (ref "U1") (pin "66") (pinfunction "VCCINT_66") (pintype "power_in"))
      (node (ref "U1") (pin "76") (pinfunction "VCCINT_76") (pintype "power_in"))
      (node (ref "U1") (pin "91") (pinfunction "VCCINT_91") (pintype "power_in"))
      (node (ref "U4") (pin "5") (pinfunction "VDD_5") (pintype "power_in"))
      (node (ref "U5") (pin "OUT") (pinfunction "OUT_OUT") (pintype "power_in"))
    )
    (net (code "147") (name "3V3") (class "Default")
      (node (ref "Cb105") (pin "-") (pinfunction "-_-") (pintype "passive"))
      (node (ref "Cb117") (pin "-") (pinfunction "-_-") (pintype "passive"))
      (node (ref "Cb12") (pin "-") (pinfunction "-_-") (pintype "passive"))
      (node (ref "Cb130") (pin "-") (pinfunction "-_-") (pintype "passive"))
      (node (ref "Cb144") (pin "-") (pinfunction "-_-") (pintype "passive"))
      (node (ref "Cb156") (pin "-") (pinfunction "-_-") (pintype "passive"))
      (node (ref "Cb170") (pin "-") (pinfunction "-_-") (pintype "passive"))
      (node (ref "Cb18") (pin "-") (pinfunction "-_-") (pintype "passive"))
      (node (ref "Cb184") (pin "-") (pinfunction "-_-") (pintype "passive"))
      (node (ref "Cb19") (pin "-") (pinfunction "-_-") (pintype "passive"))
      (node (ref "Cb197") (pin "-") (pinfunction "-_-") (pintype "passive"))
      (node (ref "Cb20") (pin "-") (pinfunction "-_-") (pintype "passive"))
      (node (ref "Cb208") (pin "-") (pinfunction "-_-") (pintype "passive"))
      (node (ref "Cb26") (pin "-") (pinfunction "-_-") (pintype "passive"))
      (node (ref "Cb39") (pin "-") (pinfunction "-_-") (pintype "passive"))
      (node (ref "Cb53") (pin "-") (pinfunction "-_-") (pintype "passive"))
      (node (ref "Cb65") (pin "-") (pinfunction "-_-") (pintype "passive"))
      (node (ref "Cb78") (pin "-") (pinfunction "-_-") (pintype "passive"))
      (node (ref "Cb92") (pin "-") (pinfunction "-_-") (pintype "passive"))
      (node (ref "CbU15") (pin "-") (pinfunction "-_-") (pintype "passive"))
      (node (ref "CbU16") (pin "-") (pinfunction "-_-") (pintype "passive"))
      (node (ref "CbU17") (pin "-") (pinfunction "-_-") (pintype "passive"))
      (node (ref "CbU18") (pin "-") (pinfunction "-_-") (pintype "passive"))
      (node (ref "CbU6") (pin "-") (pinfunction "-_-") (pintype "passive"))
      (node (ref "Cp2") (pin "-") (pinfunction "-_-") (pintype "passive"))
      (node (ref "R1") (pin "2") (pinfunction "2_2") (pintype "passive"))
      (node (ref "R13") (pin "2") (pinfunction "2_2") (pintype "passive"))
      (node (ref "R14") (pin "2") (pinfunction "2_2") (pintype "passive"))
      (node (ref "R15") (pin "2") (pinfunction "2_2") (pintype "passive"))
      (node (ref "R16") (pin "2") (pinfunction "2_2") (pintype "passive"))
      (node (ref "R17") (pin "2") (pinfunction "2_2") (pintype "passive"))
      (node (ref "R18") (pin "2") (pinfunction "2_2") (pintype "passive"))
      (node (ref "R19") (pin "2") (pinfunction "2_2") (pintype "passive"))
      (node (ref "R2") (pin "2") (pinfunction "2_2") (pintype "passive"))
      (node (ref "R20") (pin "2") (pinfunction "2_2") (pintype "passive"))
      (node (ref "R3") (pin "2") (pinfunction "2_2") (pintype "passive"))
      (node (ref "R4") (pin "2") (pinfunction "2_2") (pintype "passive"))
      (node (ref "R7") (pin "1") (pinfunction "1_1") (pintype "passive"))
      (node (ref "U1") (pin "105") (pinfunction "VCCO_105") (pintype "power_in"))
      (node (ref "U1") (pin "117") (pinfunction "VCCO_117") (pintype "power_in"))
      (node (ref "U1") (pin "12") (pinfunction "VCCO_12") (pintype "power_in"))
      (node (ref "U1") (pin "130") (pinfunction "VCCO_130") (pintype "power_in"))
      (node (ref "U1") (pin "144") (pinfunction "VCCO_144") (pintype "power_in"))
      (node (ref "U1") (pin "156") (pinfunction "VCCO_156") (pintype "power_in"))
      (node (ref "U1") (pin "170") (pinfunction "VCCO_170") (pintype "power_in"))
      (node (ref "U1") (pin "184") (pinfunction "VCCO_184") (pintype "power_in"))
      (node (ref "U1") (pin "197") (pinfunction "VCCO_197") (pintype "power_in"))
      (node (ref "U1") (pin "208") (pinfunction "VCCO_208") (pintype "power_in"))
      (node (ref "U1") (pin "26") (pinfunction "VCCO_26") (pintype "power_in"))
      (node (ref "U1") (pin "39") (pinfunction "VCCO_39") (pintype "power_in"))
      (node (ref "U1") (pin "53") (pinfunction "VCCO_53") (pintype "power_in"))
      (node (ref "U1") (pin "65") (pinfunction "VCCO_65") (pintype "power_in"))
      (node (ref "U1") (pin "78") (pinfunction "VCCO_78") (pintype "power_in"))
      (node (ref "U1") (pin "92") (pinfunction "VCCO_92") (pintype "power_in"))
      (node (ref "U15") (pin "10") (pinfunction "10_10") (pintype "passive"))
      (node (ref "U15") (pin "12") (pinfunction "12_12") (pintype "passive"))
      (node (ref "U15") (pin "14") (pinfunction "14_14") (pintype "passive"))
      (node (ref "U15") (pin "16") (pinfunction "16_16") (pintype "passive"))
      (node (ref "U16") (pin "10") (pinfunction "10_10") (pintype "passive"))
      (node (ref "U16") (pin "12") (pinfunction "12_12") (pintype "passive"))
      (node (ref "U16") (pin "14") (pinfunction "14_14") (pintype "passive"))
      (node (ref "U16") (pin "16") (pinfunction "16_16") (pintype "passive"))
      (node (ref "U17") (pin "10") (pinfunction "10_10") (pintype "passive"))
      (node (ref "U17") (pin "12") (pinfunction "12_12") (pintype "passive"))
      (node (ref "U17") (pin "14") (pinfunction "14_14") (pintype "passive"))
      (node (ref "U17") (pin "16") (pinfunction "16_16") (pintype "passive"))
      (node (ref "U18") (pin "4") (pinfunction "VCC_4") (pintype "power_in"))
      (node (ref "U2") (pin "18") (pinfunction "VCCINT_18") (pintype "power_in"))
      (node (ref "U2") (pin "19") (pinfunction "VCCO_19") (pintype "power_in"))
      (node (ref "U2") (pin "20") (pinfunction "VCCINT_20") (pintype "power_in"))
      (node (ref "U3") (pin "OUT") (pinfunction "OUT_OUT") (pintype "power_in"))
      (node (ref "U6") (pin "4") (pinfunction "VCC_4") (pintype "power_in"))
    )
    (net (code "148") (name "5V") (class "Default")
      (node (ref "CbA5") (pin "-") (pinfunction "-_-") (pintype "passive"))
      (node (ref "CbA61") (pin "-") (pinfunction "-_-") (pintype "passive"))
      (node (ref "CbA62") (pin "-") (pinfunction "-_-") (pintype "passive"))
      (node (ref "CbA8") (pin "-") (pinfunction "-_-") (pintype "passive"))
      (node (ref "CbB5") (pin "-") (pinfunction "-_-") (pintype "passive"))
      (node (ref "CbB6") (pin "-") (pinfunction "-_-") (pintype "passive"))
      (node (ref "CbB61") (pin "-") (pinfunction "-_-") (pintype "passive"))
      (node (ref "CbB62") (pin "-") (pinfunction "-_-") (pintype "passive"))
      (node (ref "CbJ1") (pin "-") (pinfunction "-_-") (pintype "passive"))
      (node (ref "CbU10") (pin "-") (pinfunction "-_-") (pintype "passive"))
      (node (ref "CbU11") (pin "-") (pinfunction "-_-") (pintype "passive"))
      (node (ref "CbU12") (pin "-") (pinfunction "-_-") (pintype "passive"))
      (node (ref "CbU13") (pin "-") (pinfunction "-_-") (pintype "passive"))
      (node (ref "CbU14") (pin "-") (pinfunction "-_-") (pintype "passive"))
      (node (ref "CbU7") (pin "-") (pinfunction "-_-") (pintype "passive"))
      (node (ref "CbU8") (pin "-") (pinfunction "-_-") (pintype "passive"))
      (node (ref "CbU9") (pin "-") (pinfunction "-_-") (pintype "passive"))
      (node (ref "Cp1") (pin "-") (pinfunction "-_-") (pintype "passive"))
      (node (ref "Cp3") (pin "-") (pinfunction "-_-") (pintype "passive"))
      (node (ref "J1") (pin "13") (pinfunction "13_13") (pintype "power_in"))
      (node (ref "J2") (pin "4") (pinfunction "5V_4") (pintype "passive"))
      (node (ref "P1") (pin "A5") (pinfunction "+5V_A5") (pintype "power_in"))
      (node (ref "P1") (pin "A61") (pinfunction "+5V_A61") (pintype "power_in"))
      (node (ref "P1") (pin "A62") (pinfunction "+5V_A62") (pintype "power_in"))
      (node (ref "P1") (pin "A8") (pinfunction "+5V_A8") (pintype "power_in"))
      (node (ref "P1") (pin "B5") (pinfunction "+5V_B5") (pintype "power_in"))
      (node (ref "P1") (pin "B6") (pinfunction "+5V_B6") (pintype "power_in"))
      (node (ref "P1") (pin "B61") (pinfunction "+5V_B61") (pintype "power_in"))
      (node (ref "P1") (pin "B62") (pinfunction "+5V_B62") (pintype "power_in"))
      (node (ref "R107") (pin "1") (pinfunction "1_1") (pintype "passive"))
      (node (ref "R34") (pin "1") (pinfunction "1_1") (pintype "passive"))
      (node (ref "R35") (pin "1") (pinfunction "1_1") (pintype "passive"))
      (node (ref "R36") (pin "1") (pinfunction "1_1") (pintype "passive"))
      (node (ref "R37") (pin "1") (pinfunction "1_1") (pintype "passive"))
      (node (ref "R38") (pin "1") (pinfunction "1_1") (pintype "passive"))
      (node (ref "R39") (pin "1") (pinfunction "1_1") (pintype "passive"))
      (node (ref "R40") (pin "1") (pinfunction "1_1") (pintype "passive"))
      (node (ref "R41") (pin "1") (pinfunction "1_1") (pintype "passive"))
      (node (ref "R42") (pin "1") (pinfunction "1_1") (pintype "passive"))
      (node (ref "R43") (pin "1") (pinfunction "1_1") (pintype "passive"))
      (node (ref "R44") (pin "1") (pinfunction "1_1") (pintype "passive"))
      (node (ref "R45") (pin "1") (pinfunction "1_1") (pintype "passive"))
      (node (ref "R63") (pin "2") (pinfunction "2_2") (pintype "passive"))
      (node (ref "R64") (pin "2") (pinfunction "2_2") (pintype "passive"))
      (node (ref "R65") (pin "2") (pinfunction "2_2") (pintype "passive"))
      (node (ref "R66") (pin "2") (pinfunction "2_2") (pintype "passive"))
      (node (ref "R67") (pin "2") (pinfunction "2_2") (pintype "passive"))
      (node (ref "R68") (pin "2") (pinfunction "2_2") (pintype "passive"))
      (node (ref "R69") (pin "2") (pinfunction "2_2") (pintype "passive"))
      (node (ref "R70") (pin "2") (pinfunction "2_2") (pintype "passive"))
      (node (ref "R71") (pin "2") (pinfunction "2_2") (pintype "passive"))
      (node (ref "R72") (pin "2") (pinfunction "2_2") (pintype "passive"))
      (node (ref "R73") (pin "2") (pinfunction "2_2") (pintype "passive"))
      (node (ref "R74") (pin "2") (pinfunction "2_2") (pintype "passive"))
      (node (ref "U10") (pin "1") (pinfunction "1_1") (pintype "power_in"))
      (node (ref "U11") (pin "1") (pinfunction "1_1") (pintype "power_in"))
      (node (ref "U12") (pin "1") (pinfunction "1_1") (pintype "power_in"))
      (node (ref "U13") (pin "14") (pinfunction "14_14") (pintype "power_in"))
      (node (ref "U14") (pin "14") (pinfunction "14_14") (pintype "power_in"))
      (node (ref "U3") (pin "IN") (pinfunction "IN_IN") (pintype "power_in"))
      (node (ref "U3") (pin "SHDN") (pinfunction "~{SHDN}_SHDN") (pintype "passive"))
      (node (ref "U5") (pin "IN") (pinfunction "IN_IN") (pintype "power_in"))
      (node (ref "U5") (pin "SHDN") (pinfunction "~{SHDN}_SHDN") (pintype "passive"))
      (node (ref "U7") (pin "1") (pinfunction "1_1") (pintype "power_in"))
      (node (ref "U8") (pin "1") (pinfunction "1_1") (pintype "power_in"))
      (node (ref "U9") (pin "1") (pinfunction "1_1") (pintype "power_in"))
    )
    (net (code "149") (name "GND") (class "Default")
      (node (ref "C1") (pin "1") (pinfunction "1_1") (pintype "passive"))
      (node (ref "Cb105") (pin "+") (pinfunction "+_+") (pintype "passive"))
      (node (ref "Cb117") (pin "+") (pinfunction "+_+") (pintype "passive"))
      (node (ref "Cb118") (pin "+") (pinfunction "+_+") (pintype "passive"))
      (node (ref "Cb12") (pin "+") (pinfunction "+_+") (pintype "passive"))
      (node (ref "Cb128") (pin "+") (pinfunction "+_+") (pintype "passive"))
      (node (ref "Cb13") (pin "+") (pinfunction "+_+") (pintype "passive"))
      (node (ref "Cb130") (pin "+") (pinfunction "+_+") (pintype "passive"))
      (node (ref "Cb143") (pin "+") (pinfunction "+_+") (pintype "passive"))
      (node (ref "Cb144") (pin "+") (pinfunction "+_+") (pintype "passive"))
      (node (ref "Cb156") (pin "+") (pinfunction "+_+") (pintype "passive"))
      (node (ref "Cb170") (pin "+") (pinfunction "+_+") (pintype "passive"))
      (node (ref "Cb171") (pin "+") (pinfunction "+_+") (pintype "passive"))
      (node (ref "Cb18") (pin "+") (pinfunction "+_+") (pintype "passive"))
      (node (ref "Cb184") (pin "+") (pinfunction "+_+") (pintype "passive"))
      (node (ref "Cb186") (pin "+") (pinfunction "+_+") (pintype "passive"))
      (node (ref "Cb19") (pin "+") (pinfunction "+_+") (pintype "passive"))
      (node (ref "Cb196") (pin "+") (pinfunction "+_+") (pintype "passive"))
      (node (ref "Cb197") (pin "+") (pinfunction "+_+") (pintype "passive"))
      (node (ref "Cb20") (pin "+") (pinfunction "+_+") (pintype "passive"))
      (node (ref "Cb208") (pin "+") (pinfunction "+_+") (pintype "passive"))
      (node (ref "Cb26") (pin "+") (pinfunction "+_+") (pintype "passive"))
      (node (ref "Cb28") (pin "+") (pinfunction "+_+") (pintype "passive"))
      (node (ref "Cb38") (pin "+") (pinfunction "+_+") (pintype "passive"))
      (node (ref "Cb39") (pin "+") (pinfunction "+_+") (pintype "passive"))
      (node (ref "Cb53") (pin "+") (pinfunction "+_+") (pintype "passive"))
      (node (ref "Cb65") (pin "+") (pinfunction "+_+") (pintype "passive"))
      (node (ref "Cb66") (pin "+") (pinfunction "+_+") (pintype "passive"))
      (node (ref "Cb76") (pin "+") (pinfunction "+_+") (pintype "passive"))
      (node (ref "Cb78") (pin "+") (pinfunction "+_+") (pintype "passive"))
      (node (ref "Cb91") (pin "+") (pinfunction "+_+") (pintype "passive"))
      (node (ref "Cb92") (pin "+") (pinfunction "+_+") (pintype "passive"))
      (node (ref "CbA10") (pin "+") (pinfunction "+_+") (pintype "passive"))
      (node (ref "CbA16") (pin "+") (pinfunction "+_+") (pintype "passive"))
      (node (ref "CbA21") (pin "+") (pinfunction "+_+") (pintype "passive"))
      (node (ref "CbA27") (pin "+") (pinfunction "+_+") (pintype "passive"))
      (node (ref "CbA33") (pin "+") (pinfunction "+_+") (pintype "passive"))
      (node (ref "CbA39") (pin "+") (pinfunction "+_+") (pintype "passive"))
      (node (ref "CbA45") (pin "+") (pinfunction "+_+") (pintype "passive"))
      (node (ref "CbA5") (pin "+") (pinfunction "+_+") (pintype "passive"))
      (node (ref "CbA53") (pin "+") (pinfunction "+_+") (pintype "passive"))
      (node (ref "CbA59") (pin "+") (pinfunction "+_+") (pintype "passive"))
      (node (ref "CbA61") (pin "+") (pinfunction "+_+") (pintype "passive"))
      (node (ref "CbA62") (pin "+") (pinfunction "+_+") (pintype "passive"))
      (node (ref "CbA8") (pin "+") (pinfunction "+_+") (pintype "passive"))
      (node (ref "CbB19") (pin "+") (pinfunction "+_+") (pintype "passive"))
      (node (ref "CbB25") (pin "+") (pinfunction "+_+") (pintype "passive"))
      (node (ref "CbB31") (pin "+") (pinfunction "+_+") (pintype "passive"))
      (node (ref "CbB36") (pin "+") (pinfunction "+_+") (pintype "passive"))
      (node (ref "CbB41") (pin "+") (pinfunction "+_+") (pintype "passive"))
      (node (ref "CbB43") (pin "+") (pinfunction "+_+") (pintype "passive"))
      (node (ref "CbB5") (pin "+") (pinfunction "+_+") (pintype "passive"))
      (node (ref "CbB54") (pin "+") (pinfunction "+_+") (pintype "passive"))
      (node (ref "CbB59") (pin "+") (pinfunction "+_+") (pintype "passive"))
      (node (ref "CbB6") (pin "+") (pinfunction "+_+") (pintype "passive"))
      (node (ref "CbB61") (pin "+") (pinfunction "+_+") (pintype "passive"))
      (node (ref "CbB62") (pin "+") (pinfunction "+_+") (pintype "passive"))
      (node (ref "CbJ") (pin "+") (pinfunction "+_+") (pintype "passive"))
      (node (ref "CbJ1") (pin "+") (pinfunction "+_+") (pintype "passive"))
      (node (ref "CbU10") (pin "+") (pinfunction "+_+") (pintype "passive"))
      (node (ref "CbU11") (pin "+") (pinfunction "+_+") (pintype "passive"))
      (node (ref "CbU12") (pin "+") (pinfunction "+_+") (pintype "passive"))
      (node (ref "CbU13") (pin "+") (pinfunction "+_+") (pintype "passive"))
      (node (ref "CbU14") (pin "+") (pinfunction "+_+") (pintype "passive"))
      (node (ref "CbU15") (pin "+") (pinfunction "+_+") (pintype "passive"))
      (node (ref "CbU16") (pin "+") (pinfunction "+_+") (pintype "passive"))
      (node (ref "CbU17") (pin "+") (pinfunction "+_+") (pintype "passive"))
      (node (ref "CbU18") (pin "+") (pinfunction "+_+") (pintype "passive"))
      (node (ref "CbU4") (pin "+") (pinfunction "+_+") (pintype "passive"))
      (node (ref "CbU6") (pin "+") (pinfunction "+_+") (pintype "passive"))
      (node (ref "CbU7") (pin "+") (pinfunction "+_+") (pintype "passive"))
      (node (ref "CbU8") (pin "+") (pinfunction "+_+") (pintype "passive"))
      (node (ref "CbU9") (pin "+") (pinfunction "+_+") (pintype "passive"))
      (node (ref "Cp1") (pin "+") (pinfunction "+_+") (pintype "passive"))
      (node (ref "Cp2") (pin "+") (pinfunction "+_+") (pintype "passive"))
      (node (ref "Cp3") (pin "+") (pinfunction "+_+") (pintype "passive"))
      (node (ref "Cp4") (pin "+") (pinfunction "+_+") (pintype "passive"))
      (node (ref "J1") (pin "38") (pinfunction "38_38") (pintype "power_in"))
      (node (ref "J2") (pin "2") (pinfunction "G_2") (pintype "passive"))
      (node (ref "J2") (pin "3") (pinfunction "G_3") (pintype "passive"))
      (node (ref "JTAG") (pin "10") (pinfunction "GND_10") (pintype "power_in"))
      (node (ref "JTAG") (pin "2") (pinfunction "GND_2") (pintype "power_in"))
      (node (ref "JTAG") (pin "6") (pinfunction "GND_6") (pintype "passive"))
      (node (ref "JTAG") (pin "7") (pinfunction "GND_7") (pintype "passive"))
      (node (ref "JTAG") (pin "8") (pinfunction "GND_8") (pintype "passive"))
      (node (ref "M0") (pin "1") (pinfunction "C1_1") (pintype "passive"))
      (node (ref "M1") (pin "1") (pinfunction "C1_1") (pintype "passive"))
      (node (ref "M2") (pin "1") (pinfunction "C1_1") (pintype "passive"))
      (node (ref "O1E") (pin "1") (pinfunction "C1_1") (pintype "passive"))
      (node (ref "O2E") (pin "1") (pinfunction "C1_1") (pintype "passive"))
      (node (ref "P1") (pin "A18") (pinfunction "GND_A18") (pintype "power_in"))
      (node (ref "P1") (pin "A24") (pinfunction "GND_A24") (pintype "power_in"))
      (node (ref "P1") (pin "A30") (pinfunction "GND_A30") (pintype "power_in"))
      (node (ref "P1") (pin "A35") (pinfunction "GND_A35") (pintype "power_in"))
      (node (ref "P1") (pin "A37") (pinfunction "GND_A37") (pintype "power_in"))
      (node (ref "P1") (pin "A42") (pinfunction "GND_A42") (pintype "power_in"))
      (node (ref "P1") (pin "A48") (pinfunction "GND_A48") (pintype "power_in"))
      (node (ref "P1") (pin "A56") (pinfunction "GND_A56") (pintype "power_in"))
      (node (ref "P1") (pin "B15") (pinfunction "GND_B15") (pintype "power_in"))
      (node (ref "P1") (pin "B17") (pinfunction "GND_B17") (pintype "power_in"))
      (node (ref "P1") (pin "B22") (pinfunction "GND_B22") (pintype "power_in"))
      (node (ref "P1") (pin "B28") (pinfunction "GND_B28") (pintype "power_in"))
      (node (ref "P1") (pin "B3") (pinfunction "GND_B3") (pintype "power_in"))
      (node (ref "P1") (pin "B34") (pinfunction "GND_B34") (pintype "power_in"))
      (node (ref "P1") (pin "B38") (pinfunction "GND_B38") (pintype "power_in"))
      (node (ref "P1") (pin "B46") (pinfunction "GND_B46") (pintype "power_in"))
      (node (ref "P1") (pin "B49") (pinfunction "GND_B49") (pintype "power_in"))
      (node (ref "P1") (pin "B57") (pinfunction "GND_B57") (pintype "power_in"))
      (node (ref "Q1") (pin "2") (pinfunction "E_2") (pintype "passive"))
      (node (ref "Q2") (pin "2") (pinfunction "E_2") (pintype "passive"))
      (node (ref "Q3") (pin "2") (pinfunction "E_2") (pintype "passive"))
      (node (ref "Q4") (pin "2") (pinfunction "E_2") (pintype "passive"))
      (node (ref "Q5") (pin "2") (pinfunction "E_2") (pintype "passive"))
      (node (ref "Q6") (pin "2") (pinfunction "E_2") (pintype "passive"))
      (node (ref "Q7") (pin "2") (pinfunction "E_2") (pintype "passive"))
      (node (ref "Q8") (pin "2") (pinfunction "E_2") (pintype "passive"))
      (node (ref "Q9") (pin "2") (pinfunction "E_2") (pintype "passive"))
      (node (ref "R10") (pin "2") (pinfunction "2_2") (pintype "passive"))
      (node (ref "R100") (pin "1") (pinfunction "1_1") (pintype "passive"))
      (node (ref "R101") (pin "1") (pinfunction "1_1") (pintype "passive"))
      (node (ref "R102") (pin "1") (pinfunction "1_1") (pintype "passive"))
      (node (ref "R103") (pin "1") (pinfunction "1_1") (pintype "passive"))
      (node (ref "R104") (pin "1") (pinfunction "1_1") (pintype "passive"))
      (node (ref "R105") (pin "1") (pinfunction "1_1") (pintype "passive"))
      (node (ref "R106") (pin "1") (pinfunction "1_1") (pintype "passive"))
      (node (ref "R107") (pin "2") (pinfunction "2_2") (pintype "passive"))
      (node (ref "R21") (pin "1") (pinfunction "1_1") (pintype "passive"))
      (node (ref "R22") (pin "2") (pinfunction "2_2") (pintype "passive"))
      (node (ref "R23") (pin "2") (pinfunction "2_2") (pintype "passive"))
      (node (ref "R24") (pin "2") (pinfunction "2_2") (pintype "passive"))
      (node (ref "R25") (pin "2") (pinfunction "2_2") (pintype "passive"))
      (node (ref "R26") (pin "2") (pinfunction "2_2") (pintype "passive"))
      (node (ref "R27") (pin "2") (pinfunction "2_2") (pintype "passive"))
      (node (ref "R28") (pin "2") (pinfunction "2_2") (pintype "passive"))
      (node (ref "R29") (pin "2") (pinfunction "2_2") (pintype "passive"))
      (node (ref "R30") (pin "2") (pinfunction "2_2") (pintype "passive"))
      (node (ref "R31") (pin "2") (pinfunction "2_2") (pintype "passive"))
      (node (ref "R32") (pin "2") (pinfunction "2_2") (pintype "passive"))
      (node (ref "R33") (pin "2") (pinfunction "2_2") (pintype "passive"))
      (node (ref "R5") (pin "1") (pinfunction "1_1") (pintype "passive"))
      (node (ref "R59") (pin "2") (pinfunction "2_2") (pintype "passive"))
      (node (ref "R6") (pin "1") (pinfunction "1_1") (pintype "passive"))
      (node (ref "R60") (pin "1") (pinfunction "1_1") (pintype "passive"))
      (node (ref "R61") (pin "2") (pinfunction "2_2") (pintype "passive"))
      (node (ref "R62") (pin "1") (pinfunction "1_1") (pintype "passive"))
      (node (ref "R75") (pin "1") (pinfunction "1_1") (pintype "passive"))
      (node (ref "R76") (pin "2") (pinfunction "2_2") (pintype "passive"))
      (node (ref "R77") (pin "1") (pinfunction "1_1") (pintype "passive"))
      (node (ref "R78") (pin "2") (pinfunction "2_2") (pintype "passive"))
      (node (ref "R79") (pin "1") (pinfunction "1_1") (pintype "passive"))
      (node (ref "R8") (pin "2") (pinfunction "2_2") (pintype "passive"))
      (node (ref "R80") (pin "2") (pinfunction "2_2") (pintype "passive"))
      (node (ref "R81") (pin "2") (pinfunction "2_2") (pintype "passive"))
      (node (ref "R82") (pin "1") (pinfunction "1_1") (pintype "passive"))
      (node (ref "R87") (pin "1") (pinfunction "1_1") (pintype "passive"))
      (node (ref "R88") (pin "1") (pinfunction "1_1") (pintype "passive"))
      (node (ref "R89") (pin "1") (pinfunction "1_1") (pintype "passive"))
      (node (ref "R90") (pin "1") (pinfunction "1_1") (pintype "passive"))
      (node (ref "R99") (pin "1") (pinfunction "1_1") (pintype "passive"))
      (node (ref "S1") (pin "C1") (pinfunction "C1_C1") (pintype "passive"))
      (node (ref "S1") (pin "C2") (pinfunction "C2_C2") (pintype "passive"))
      (node (ref "S2") (pin "C1") (pinfunction "C1_C1") (pintype "passive"))
      (node (ref "S2") (pin "C2") (pinfunction "C2_C2") (pintype "passive"))
      (node (ref "U1") (pin "1") (pinfunction "GND_1") (pintype "power_in"))
      (node (ref "U1") (pin "103") (pinfunction "GND_103") (pintype "power_in"))
      (node (ref "U1") (pin "11") (pinfunction "GND_11") (pintype "power_in"))
      (node (ref "U1") (pin "116") (pinfunction "GND_116") (pintype "power_in"))
      (node (ref "U1") (pin "124") (pinfunction "GND_124") (pintype "power_in"))
      (node (ref "U1") (pin "131") (pinfunction "GND_131") (pintype "power_in"))
      (node (ref "U1") (pin "137") (pinfunction "GND_137") (pintype "power_in"))
      (node (ref "U1") (pin "145") (pinfunction "GND_145") (pintype "power_in"))
      (node (ref "U1") (pin "158") (pinfunction "GND_158") (pintype "power_in"))
      (node (ref "U1") (pin "169") (pinfunction "GND_169") (pintype "power_in"))
      (node (ref "U1") (pin "177") (pinfunction "GND_177") (pintype "power_in"))
      (node (ref "U1") (pin "183") (pinfunction "GND_183") (pintype "power_in"))
      (node (ref "U1") (pin "19") (pinfunction "GND_19") (pintype "power_in"))
      (node (ref "U1") (pin "190") (pinfunction "GND_190") (pintype "power_in"))
      (node (ref "U1") (pin "198") (pinfunction "GND_198") (pintype "power_in"))
      (node (ref "U1") (pin "25") (pinfunction "GND_25") (pintype "power_in"))
      (node (ref "U1") (pin "32") (pinfunction "GND_32") (pintype "power_in"))
      (node (ref "U1") (pin "40") (pinfunction "GND_40") (pintype "power_in"))
      (node (ref "U1") (pin "51") (pinfunction "GND_51") (pintype "power_in"))
      (node (ref "U1") (pin "64") (pinfunction "GND_64") (pintype "power_in"))
      (node (ref "U1") (pin "72") (pinfunction "GND_72") (pintype "power_in"))
      (node (ref "U1") (pin "79") (pinfunction "GND_79") (pintype "power_in"))
      (node (ref "U1") (pin "85") (pinfunction "GND_85") (pintype "power_in"))
      (node (ref "U1") (pin "93") (pinfunction "GND_93") (pintype "power_in"))
      (node (ref "U10") (pin "4") (pinfunction "4_4") (pintype "power_in"))
      (node (ref "U11") (pin "4") (pinfunction "4_4") (pintype "power_in"))
      (node (ref "U12") (pin "4") (pinfunction "4_4") (pintype "power_in"))
      (node (ref "U13") (pin "7") (pinfunction "7_7") (pintype "power_in"))
      (node (ref "U14") (pin "7") (pinfunction "7_7") (pintype "power_in"))
      (node (ref "U15") (pin "2") (pinfunction "2_2") (pintype "passive"))
      (node (ref "U15") (pin "4") (pinfunction "4_4") (pintype "passive"))
      (node (ref "U15") (pin "6") (pinfunction "6_6") (pintype "passive"))
      (node (ref "U15") (pin "8") (pinfunction "8_8") (pintype "passive"))
      (node (ref "U16") (pin "2") (pinfunction "2_2") (pintype "passive"))
      (node (ref "U16") (pin "4") (pinfunction "4_4") (pintype "passive"))
      (node (ref "U16") (pin "6") (pinfunction "6_6") (pintype "passive"))
      (node (ref "U16") (pin "8") (pinfunction "8_8") (pintype "passive"))
      (node (ref "U17") (pin "2") (pinfunction "2_2") (pintype "passive"))
      (node (ref "U17") (pin "4") (pinfunction "4_4") (pintype "passive"))
      (node (ref "U17") (pin "6") (pinfunction "6_6") (pintype "passive"))
      (node (ref "U17") (pin "8") (pinfunction "8_8") (pintype "passive"))
      (node (ref "U18") (pin "2") (pinfunction "G_2") (pintype "power_in"))
      (node (ref "U2") (pin "11") (pinfunction "GND_11") (pintype "power_in"))
      (node (ref "U3") (pin "G") (pinfunction "G_G") (pintype "power_in"))
      (node (ref "U4") (pin "2") (pinfunction "GND_2") (pintype "power_in"))
      (node (ref "U5") (pin "G") (pinfunction "G_G") (pintype "power_in"))
      (node (ref "U6") (pin "2") (pinfunction "G_2") (pintype "power_in"))
      (node (ref "U7") (pin "4") (pinfunction "4_4") (pintype "power_in"))
      (node (ref "U8") (pin "4") (pinfunction "4_4") (pintype "power_in"))
      (node (ref "U9") (pin "4") (pinfunction "4_4") (pintype "power_in"))
    )
    (net (code "150") (name "Net-(CbA10-Pad-)") (class "Default")
      (node (ref "CbA10") (pin "-") (pinfunction "-_-") (pintype "passive"))
      (node (ref "P1") (pin "A10") (pinfunction "IOPWR_A10") (pintype "power_in"))
    )
    (net (code "151") (name "Net-(CbA16-Pad-)") (class "Default")
      (node (ref "CbA16") (pin "-") (pinfunction "-_-") (pintype "passive"))
      (node (ref "P1") (pin "A16") (pinfunction "IOPWR_A16") (pintype "power_in"))
    )
    (net (code "152") (name "Net-(CbA21-Pad-)") (class "Default")
      (node (ref "CbA21") (pin "-") (pinfunction "-_-") (pintype "passive"))
      (node (ref "P1") (pin "A21") (pinfunction "+3.3V_A21") (pintype "power_in"))
    )
    (net (code "153") (name "Net-(CbA27-Pad-)") (class "Default")
      (node (ref "CbA27") (pin "-") (pinfunction "-_-") (pintype "passive"))
      (node (ref "P1") (pin "A27") (pinfunction "+3.3V_A27") (pintype "power_in"))
    )
    (net (code "154") (name "Net-(CbA33-Pad-)") (class "Default")
      (node (ref "CbA33") (pin "-") (pinfunction "-_-") (pintype "passive"))
      (node (ref "P1") (pin "A33") (pinfunction "+3.3V_A33") (pintype "power_in"))
    )
    (net (code "155") (name "Net-(CbA39-Pad-)") (class "Default")
      (node (ref "CbA39") (pin "-") (pinfunction "-_-") (pintype "passive"))
      (node (ref "P1") (pin "A39") (pinfunction "+3.3V_A39") (pintype "power_in"))
    )
    (net (code "156") (name "Net-(CbA45-Pad-)") (class "Default")
      (node (ref "CbA45") (pin "-") (pinfunction "-_-") (pintype "passive"))
      (node (ref "P1") (pin "A45") (pinfunction "+3.3V_A45") (pintype "power_in"))
    )
    (net (code "157") (name "Net-(CbA53-Pad-)") (class "Default")
      (node (ref "CbA53") (pin "-") (pinfunction "-_-") (pintype "passive"))
      (node (ref "P1") (pin "A53") (pinfunction "+3.3V_A53") (pintype "power_in"))
    )
    (net (code "158") (name "Net-(CbA59-Pad-)") (class "Default")
      (node (ref "CbA59") (pin "-") (pinfunction "-_-") (pintype "passive"))
      (node (ref "P1") (pin "A59") (pinfunction "IOPWR_A59") (pintype "power_in"))
    )
    (net (code "159") (name "Net-(CbB19-Pad-)") (class "Default")
      (node (ref "CbB19") (pin "-") (pinfunction "-_-") (pintype "passive"))
      (node (ref "P1") (pin "B19") (pinfunction "IOPWR_B19") (pintype "power_in"))
    )
    (net (code "160") (name "Net-(CbB25-Pad-)") (class "Default")
      (node (ref "CbB25") (pin "-") (pinfunction "-_-") (pintype "passive"))
      (node (ref "P1") (pin "B25") (pinfunction "+3.3V_B25") (pintype "power_in"))
    )
    (net (code "161") (name "Net-(CbB31-Pad-)") (class "Default")
      (node (ref "CbB31") (pin "-") (pinfunction "-_-") (pintype "passive"))
      (node (ref "P1") (pin "B31") (pinfunction "+3.3V_B31") (pintype "power_in"))
    )
    (net (code "162") (name "Net-(CbB36-Pad-)") (class "Default")
      (node (ref "CbB36") (pin "-") (pinfunction "-_-") (pintype "passive"))
      (node (ref "P1") (pin "B36") (pinfunction "+3.3V_B36") (pintype "power_in"))
    )
    (net (code "163") (name "Net-(CbB41-Pad-)") (class "Default")
      (node (ref "CbB41") (pin "-") (pinfunction "-_-") (pintype "passive"))
      (node (ref "P1") (pin "B41") (pinfunction "+3.3V_B41") (pintype "power_in"))
    )
    (net (code "164") (name "Net-(CbB43-Pad-)") (class "Default")
      (node (ref "CbB43") (pin "-") (pinfunction "-_-") (pintype "passive"))
      (node (ref "P1") (pin "B43") (pinfunction "+3.3V_B43") (pintype "power_in"))
    )
    (net (code "165") (name "Net-(CbB54-Pad-)") (class "Default")
      (node (ref "CbB54") (pin "-") (pinfunction "-_-") (pintype "passive"))
      (node (ref "P1") (pin "B54") (pinfunction "+3.3V_B54") (pintype "power_in"))
    )
    (net (code "166") (name "Net-(CbB59-Pad-)") (class "Default")
      (node (ref "CbB59") (pin "-") (pinfunction "-_-") (pintype "passive"))
      (node (ref "P1") (pin "B59") (pinfunction "IOPWR_B59") (pintype "power_in"))
    )
    (net (code "167") (name "Net-(D1-A)") (class "Default")
      (node (ref "D1") (pin "1") (pinfunction "A_1") (pintype "passive"))
      (node (ref "R4") (pin "1") (pinfunction "1_1") (pintype "passive"))
    )
    (net (code "168") (name "Net-(D1-K)") (class "Default")
      (node (ref "D1") (pin "2") (pinfunction "K_2") (pintype "passive"))
      (node (ref "Q1") (pin "3") (pinfunction "C_3") (pintype "passive"))
    )
    (net (code "169") (name "Net-(D2-A)") (class "Default")
      (node (ref "D2") (pin "1") (pinfunction "A_1") (pintype "passive"))
      (node (ref "R13") (pin "1") (pinfunction "1_1") (pintype "passive"))
    )
    (net (code "170") (name "Net-(D2-K)") (class "Default")
      (node (ref "D2") (pin "2") (pinfunction "K_2") (pintype "passive"))
      (node (ref "Q2") (pin "3") (pinfunction "C_3") (pintype "passive"))
    )
    (net (code "171") (name "Net-(D3-A)") (class "Default")
      (node (ref "D3") (pin "1") (pinfunction "A_1") (pintype "passive"))
      (node (ref "R14") (pin "1") (pinfunction "1_1") (pintype "passive"))
    )
    (net (code "172") (name "Net-(D3-K)") (class "Default")
      (node (ref "D3") (pin "2") (pinfunction "K_2") (pintype "passive"))
      (node (ref "Q3") (pin "3") (pinfunction "C_3") (pintype "passive"))
    )
    (net (code "173") (name "Net-(D4-A)") (class "Default")
      (node (ref "D4") (pin "1") (pinfunction "A_1") (pintype "passive"))
      (node (ref "R15") (pin "1") (pinfunction "1_1") (pintype "passive"))
    )
    (net (code "174") (name "Net-(D4-K)") (class "Default")
      (node (ref "D4") (pin "2") (pinfunction "K_2") (pintype "passive"))
      (node (ref "Q4") (pin "3") (pinfunction "C_3") (pintype "passive"))
    )
    (net (code "175") (name "Net-(D5-A)") (class "Default")
      (node (ref "D5") (pin "1") (pinfunction "A_1") (pintype "passive"))
      (node (ref "R16") (pin "1") (pinfunction "1_1") (pintype "passive"))
    )
    (net (code "176") (name "Net-(D5-K)") (class "Default")
      (node (ref "D5") (pin "2") (pinfunction "K_2") (pintype "passive"))
      (node (ref "Q5") (pin "3") (pinfunction "C_3") (pintype "passive"))
    )
    (net (code "177") (name "Net-(D6-A)") (class "Default")
      (node (ref "D6") (pin "1") (pinfunction "A_1") (pintype "passive"))
      (node (ref "R17") (pin "1") (pinfunction "1_1") (pintype "passive"))
    )
    (net (code "178") (name "Net-(D6-K)") (class "Default")
      (node (ref "D6") (pin "2") (pinfunction "K_2") (pintype "passive"))
      (node (ref "Q6") (pin "3") (pinfunction "C_3") (pintype "passive"))
    )
    (net (code "179") (name "Net-(D7-A)") (class "Default")
      (node (ref "D7") (pin "1") (pinfunction "A_1") (pintype "passive"))
      (node (ref "R18") (pin "1") (pinfunction "1_1") (pintype "passive"))
    )
    (net (code "180") (name "Net-(D7-K)") (class "Default")
      (node (ref "D7") (pin "2") (pinfunction "K_2") (pintype "passive"))
      (node (ref "Q7") (pin "3") (pinfunction "C_3") (pintype "passive"))
    )
    (net (code "181") (name "Net-(D8-A)") (class "Default")
      (node (ref "D8") (pin "1") (pinfunction "A_1") (pintype "passive"))
      (node (ref "R19") (pin "1") (pinfunction "1_1") (pintype "passive"))
    )
    (net (code "182") (name "Net-(D8-K)") (class "Default")
      (node (ref "D8") (pin "2") (pinfunction "K_2") (pintype "passive"))
      (node (ref "Q8") (pin "3") (pinfunction "C_3") (pintype "passive"))
    )
    (net (code "183") (name "Net-(D9-A)") (class "Default")
      (node (ref "D9") (pin "1") (pinfunction "A_1") (pintype "passive"))
      (node (ref "R20") (pin "1") (pinfunction "1_1") (pintype "passive"))
    )
    (net (code "184") (name "Net-(D9-K)") (class "Default")
      (node (ref "D9") (pin "2") (pinfunction "K_2") (pintype "passive"))
      (node (ref "Q9") (pin "3") (pinfunction "C_3") (pintype "passive"))
    )
    (net (code "185") (name "Net-(J1-MH1)") (class "Default")
      (node (ref "C1") (pin "2") (pinfunction "2_2") (pintype "passive"))
      (node (ref "J1") (pin "51") (pinfunction "MH1_51") (pintype "power_in"))
      (node (ref "J1") (pin "52") (pinfunction "MH2_52") (pintype "power_in"))
      (node (ref "R21") (pin "2") (pinfunction "2_2") (pintype "passive"))
    )
    (net (code "186") (name "Net-(JTAG-TCK)") (class "Default")
      (node (ref "JTAG") (pin "1") (pinfunction "TCK_1") (pintype "output"))
      (node (ref "U1") (pin "207") (pinfunction "TCK_207") (pintype "bidirectional"))
      (node (ref "U2") (pin "6") (pinfunction "TCK_6") (pintype "input"))
    )
    (net (code "187") (name "Net-(JTAG-TDI)") (class "Default")
      (node (ref "JTAG") (pin "9") (pinfunction "TDI_9") (pintype "output"))
      (node (ref "U2") (pin "4") (pinfunction "TDI_4") (pintype "input"))
    )
    (net (code "188") (name "Net-(JTAG-TDO)") (class "Default")
      (node (ref "JTAG") (pin "3") (pinfunction "TDO_3") (pintype "input"))
      (node (ref "U1") (pin "157") (pinfunction "TDO_157") (pintype "bidirectional"))
    )
    (net (code "189") (name "Net-(JTAG-TMS)") (class "Default")
      (node (ref "JTAG") (pin "5") (pinfunction "TMS_5") (pintype "output"))
      (node (ref "U1") (pin "2") (pinfunction "TMS_2") (pintype "bidirectional"))
      (node (ref "U2") (pin "5") (pinfunction "TMS_5") (pintype "input"))
    )
    (net (code "190") (name "Net-(M0-C2)") (class "Default")
      (node (ref "M0") (pin "2") (pinfunction "C2_2") (pintype "passive"))
      (node (ref "U1") (pin "52") (pinfunction "M0_(291)_52") (pintype "input"))
    )
    (net (code "191") (name "Net-(M1-C2)") (class "Default")
      (node (ref "M1") (pin "2") (pinfunction "C2_2") (pintype "passive"))
      (node (ref "U1") (pin "50") (pinfunction "M1_(290)_50") (pintype "input"))
    )
    (net (code "192") (name "Net-(M2-C2)") (class "Default")
      (node (ref "M2") (pin "2") (pinfunction "C2_2") (pintype "passive"))
      (node (ref "U1") (pin "54") (pinfunction "M2_(292)_54") (pintype "input"))
    )
    (net (code "193") (name "Net-(O1E-C2)") (class "Default")
      (node (ref "O1E") (pin "2") (pinfunction "C2_2") (pintype "passive"))
      (node (ref "U6") (pin "1") (pinfunction "EOH_1") (pintype "tri_state"))
    )
    (net (code "194") (name "Net-(O2E-C2)") (class "Default")
      (node (ref "O2E") (pin "2") (pinfunction "C2_2") (pintype "passive"))
      (node (ref "U18") (pin "1") (pinfunction "EOH_1") (pintype "tri_state"))
    )
    (net (code "195") (name "Net-(P1-PRSNT1#)") (class "Default")
      (node (ref "P1") (pin "B9") (pinfunction "PRSNT1#_B9") (pintype "passive"))
      (node (ref "R5") (pin "2") (pinfunction "2_2") (pintype "passive"))
    )
    (net (code "196") (name "Net-(P1-PRSNT2#)") (class "Default")
      (node (ref "P1") (pin "B11") (pinfunction "PRSNT2#_B11") (pintype "passive"))
      (node (ref "R6") (pin "2") (pinfunction "2_2") (pintype "passive"))
    )
    (net (code "197") (name "Net-(P1-TDI)") (class "Default")
      (node (ref "P1") (pin "A4") (pinfunction "TDI_A4") (pintype "output"))
      (node (ref "P1") (pin "B4") (pinfunction "TDO_B4") (pintype "input"))
    )
    (net (code "198") (name "Net-(Q1-B)") (class "Default")
      (node (ref "Q1") (pin "1") (pinfunction "B_1") (pintype "passive"))
      (node (ref "R2") (pin "1") (pinfunction "1_1") (pintype "passive"))
      (node (ref "U1") (pin "104") (pinfunction "DONE_(439)_104") (pintype "bidirectional"))
      (node (ref "U2") (pin "10") (pinfunction "~{CE}_10") (pintype "input"))
    )
    (net (code "199") (name "Net-(R7-Pad2)") (class "Default")
      (node (ref "R7") (pin "2") (pinfunction "2_2") (pintype "passive"))
      (node (ref "R8") (pin "1") (pinfunction "1_1") (pintype "passive"))
      (node (ref "U3") (pin "SENSE") (pinfunction "SENSE_SENSE") (pintype "passive"))
    )
    (net (code "200") (name "Net-(R10-Pad1)") (class "Default")
      (node (ref "R10") (pin "1") (pinfunction "1_1") (pintype "passive"))
      (node (ref "R9") (pin "2") (pinfunction "2_2") (pintype "passive"))
      (node (ref "U5") (pin "SENSE") (pinfunction "SENSE_SENSE") (pintype "passive"))
    )
    (net (code "201") (name "Net-(R83-Pad1)") (class "Default")
      (node (ref "R83") (pin "1") (pinfunction "1_1") (pintype "passive"))
      (node (ref "U15") (pin "1") (pinfunction "1_1") (pintype "passive"))
    )
    (net (code "202") (name "Net-(R84-Pad1)") (class "Default")
      (node (ref "R84") (pin "1") (pinfunction "1_1") (pintype "passive"))
      (node (ref "U15") (pin "3") (pinfunction "3_3") (pintype "passive"))
    )
    (net (code "203") (name "Net-(R85-Pad1)") (class "Default")
      (node (ref "R85") (pin "1") (pinfunction "1_1") (pintype "passive"))
      (node (ref "U15") (pin "5") (pinfunction "5_5") (pintype "passive"))
    )
    (net (code "204") (name "Net-(R86-Pad1)") (class "Default")
      (node (ref "R86") (pin "1") (pinfunction "1_1") (pintype "passive"))
      (node (ref "U15") (pin "7") (pinfunction "7_7") (pintype "passive"))
    )
    (net (code "205") (name "Net-(R91-Pad1)") (class "Default")
      (node (ref "R91") (pin "1") (pinfunction "1_1") (pintype "passive"))
      (node (ref "U16") (pin "1") (pinfunction "1_1") (pintype "passive"))
    )
    (net (code "206") (name "Net-(R92-Pad1)") (class "Default")
      (node (ref "R92") (pin "1") (pinfunction "1_1") (pintype "passive"))
      (node (ref "U16") (pin "3") (pinfunction "3_3") (pintype "passive"))
    )
    (net (code "207") (name "Net-(R93-Pad1)") (class "Default")
      (node (ref "R93") (pin "1") (pinfunction "1_1") (pintype "passive"))
      (node (ref "U16") (pin "5") (pinfunction "5_5") (pintype "passive"))
    )
    (net (code "208") (name "Net-(R94-Pad1)") (class "Default")
      (node (ref "R94") (pin "1") (pinfunction "1_1") (pintype "passive"))
      (node (ref "U16") (pin "7") (pinfunction "7_7") (pintype "passive"))
    )
    (net (code "209") (name "Net-(R95-Pad1)") (class "Default")
      (node (ref "R95") (pin "1") (pinfunction "1_1") (pintype "passive"))
      (node (ref "U17") (pin "1") (pinfunction "1_1") (pintype "passive"))
    )
    (net (code "210") (name "Net-(R96-Pad1)") (class "Default")
      (node (ref "R96") (pin "1") (pinfunction "1_1") (pintype "passive"))
      (node (ref "U17") (pin "3") (pinfunction "3_3") (pintype "passive"))
    )
    (net (code "211") (name "Net-(R97-Pad1)") (class "Default")
      (node (ref "R97") (pin "1") (pinfunction "1_1") (pintype "passive"))
      (node (ref "U17") (pin "5") (pinfunction "5_5") (pintype "passive"))
    )
    (net (code "212") (name "Net-(R98-Pad1)") (class "Default")
      (node (ref "R98") (pin "1") (pinfunction "1_1") (pintype "passive"))
      (node (ref "U17") (pin "7") (pinfunction "7_7") (pintype "passive"))
    )
    (net (code "213") (name "Net-(U1C-I{slash}O_(DIN,_D0)_(581))") (class "Default")
      (node (ref "U1") (pin "153") (pinfunction "I/O_(DIN,_D0)_(581)_153") (pintype "bidirectional"))
      (node (ref "U2") (pin "1") (pinfunction "D0_1") (pintype "tri_state"))
    )
    (net (code "214") (name "Net-(U1D-I{slash}O_(~{INIT})_(443))") (class "Default")
      (node (ref "R1") (pin "1") (pinfunction "1_1") (pintype "passive"))
      (node (ref "U1") (pin "107") (pinfunction "I/O_(~{INIT})_(443)_107") (pintype "bidirectional"))
      (node (ref "U2") (pin "8") (pinfunction "OE/~{RESET}_8") (pintype "bidirectional"))
    )
    (net (code "215") (name "Net-(U1J-CCLK_(587))") (class "Default")
      (node (ref "U1") (pin "155") (pinfunction "CCLK_(587)_155") (pintype "bidirectional"))
      (node (ref "U2") (pin "3") (pinfunction "CLK_3") (pintype "input"))
    )
    (net (code "216") (name "Net-(U1J-PROGRAM_(442))") (class "Default")
      (node (ref "R3") (pin "1") (pinfunction "1_1") (pintype "passive"))
      (node (ref "S1") (pin "2") (pinfunction "2_2") (pintype "passive"))
      (node (ref "U1") (pin "106") (pinfunction "PROGRAM_(442)_106") (pintype "input"))
      (node (ref "U2") (pin "7") (pinfunction "D4/~{CF}_7") (pintype "tri_state"))
    )
    (net (code "217") (name "Net-(U1J-TDI)") (class "Default")
      (node (ref "U1") (pin "159") (pinfunction "TDI_159") (pintype "bidirectional"))
      (node (ref "U2") (pin "17") (pinfunction "TDO_17") (pintype "output"))
    )
    (net (code "218") (name "Net-(U4-~{MR})") (class "Default")
      (node (ref "R11") (pin "1") (pinfunction "1_1") (pintype "passive"))
      (node (ref "S2") (pin "2") (pinfunction "2_2") (pintype "passive"))
      (node (ref "U4") (pin "3") (pinfunction "~{MR}_3") (pintype "passive"))
    )
    (net (code "219") (name "unconnected-(J2-12V-Pad1)") (class "Default")
      (node (ref "J2") (pin "1") (pinfunction "12V_1") (pintype "passive+no_connect"))
    )
    (net (code "220") (name "unconnected-(P1-+12V-PadA2)") (class "Default")
      (node (ref "P1") (pin "A2") (pinfunction "+12V_A2") (pintype "power_in+no_connect"))
    )
    (net (code "221") (name "unconnected-(P1--12V-PadB1)") (class "Default")
      (node (ref "P1") (pin "B1") (pinfunction "-12V_B1") (pintype "power_in+no_connect"))
    )
    (net (code "222") (name "unconnected-(P1-3.3VAUX-PadA14)") (class "Default")
      (node (ref "P1") (pin "A14") (pinfunction "3.3VAUX_A14") (pintype "power_in+no_connect"))
    )
    (net (code "223") (name "unconnected-(P1-ACK64#-PadB60)") (class "Default")
      (node (ref "P1") (pin "B60") (pinfunction "ACK64#_B60") (pintype "bidirectional+no_connect"))
    )
    (net (code "224") (name "unconnected-(P1-INTB#-PadB7)") (class "Default")
      (node (ref "P1") (pin "B7") (pinfunction "INTB#_B7") (pintype "open_collector+no_connect"))
    )
    (net (code "225") (name "unconnected-(P1-INTC#-PadA7)") (class "Default")
      (node (ref "P1") (pin "A7") (pinfunction "INTC#_A7") (pintype "open_collector+no_connect"))
    )
    (net (code "226") (name "unconnected-(P1-INTD#-PadB8)") (class "Default")
      (node (ref "P1") (pin "B8") (pinfunction "INTD#_B8") (pintype "open_collector+no_connect"))
    )
    (net (code "227") (name "unconnected-(P1-LOCK#-PadB39)") (class "Default")
      (node (ref "P1") (pin "B39") (pinfunction "LOCK#_B39") (pintype "bidirectional+no_connect"))
    )
    (net (code "228") (name "unconnected-(P1-PME#-PadA19)") (class "Default")
      (node (ref "P1") (pin "A19") (pinfunction "PME#_A19") (pintype "open_collector+no_connect"))
    )
    (net (code "229") (name "unconnected-(P1-PadA9)") (class "Default")
      (node (ref "P1") (pin "A9") (pinfunction "A9_A9") (pintype "passive+no_connect"))
    )
    (net (code "230") (name "unconnected-(P1-PadA11)") (class "Default")
      (node (ref "P1") (pin "A11") (pinfunction "A11_A11") (pintype "passive+no_connect"))
    )
    (net (code "231") (name "unconnected-(P1-PadB10)") (class "Default")
      (node (ref "P1") (pin "B10") (pinfunction "B10_B10") (pintype "passive+no_connect"))
    )
    (net (code "232") (name "unconnected-(P1-PadB14)") (class "Default")
      (node (ref "P1") (pin "B14") (pinfunction "B14_B14") (pintype "passive+no_connect"))
    )
    (net (code "233") (name "unconnected-(P1-REQ64#-PadA60)") (class "Default")
      (node (ref "P1") (pin "A60") (pinfunction "REQ64#_A60") (pintype "bidirectional+no_connect"))
    )
    (net (code "234") (name "unconnected-(P1-SMBCLK-PadA40)") (class "Default")
      (node (ref "P1") (pin "A40") (pinfunction "SMBCLK_A40") (pintype "open_collector+no_connect"))
    )
    (net (code "235") (name "unconnected-(P1-SMBDAT-PadA41)") (class "Default")
      (node (ref "P1") (pin "A41") (pinfunction "SMBDAT_A41") (pintype "open_collector+no_connect"))
    )
    (net (code "236") (name "unconnected-(P1-TCK-PadB2)") (class "Default")
      (node (ref "P1") (pin "B2") (pinfunction "TCK_B2") (pintype "output+no_connect"))
    )
    (net (code "237") (name "unconnected-(P1-TMS-PadA3)") (class "Default")
      (node (ref "P1") (pin "A3") (pinfunction "TMS_A3") (pintype "output+no_connect"))
    )
    (net (code "238") (name "unconnected-(P1-TRST#-PadA1)") (class "Default")
      (node (ref "P1") (pin "A1") (pinfunction "TRST#_A1") (pintype "output+no_connect"))
    )
    (net (code "239") (name "unconnected-(S1-Pad1)") (class "Default")
      (node (ref "S1") (pin "1") (pinfunction "1_1") (pintype "passive+no_connect"))
    )
    (net (code "240") (name "unconnected-(S2-Pad1)") (class "Default")
      (node (ref "S2") (pin "1") (pinfunction "1_1") (pintype "passive+no_connect"))
    )
    (net (code "241") (name "unconnected-(U1A-I{slash}O,_VREF_(89)-Pad189)") (class "Default")
      (node (ref "U1") (pin "189") (pinfunction "I/O,_VREF_(89)_189") (pintype "bidirectional+no_connect"))
    )
    (net (code "242") (name "unconnected-(U1A-I{slash}O_(80)-Pad187)") (class "Default")
      (node (ref "U1") (pin "187") (pinfunction "I/O_(80)_187") (pintype "bidirectional+no_connect"))
    )
    (net (code "243") (name "unconnected-(U1A-I{slash}O_(86)-Pad188)") (class "Default")
      (node (ref "U1") (pin "188") (pinfunction "I/O_(86)_188") (pintype "bidirectional+no_connect"))
    )
    (net (code "244") (name "unconnected-(U1A-I{slash}O_(92)-Pad191)") (class "Default")
      (node (ref "U1") (pin "191") (pinfunction "I/O_(92)_191") (pintype "bidirectional+no_connect"))
    )
    (net (code "245") (name "unconnected-(U1A-I{slash}O_(95)-Pad192)") (class "Default")
      (node (ref "U1") (pin "192") (pinfunction "I/O_(95)_192") (pintype "bidirectional+no_connect"))
    )
    (net (code "246") (name "unconnected-(U1A-I{slash}O_(98)-Pad193)") (class "Default")
      (node (ref "U1") (pin "193") (pinfunction "I/O_(98)_193") (pintype "bidirectional+no_connect"))
    )
    (net (code "247") (name "unconnected-(U1A-I{slash}O_(104)-Pad194)") (class "Default")
      (node (ref "U1") (pin "194") (pinfunction "I/O_(104)_194") (pintype "bidirectional+no_connect"))
    )
    (net (code "248") (name "unconnected-(U1A-I{slash}O_(122)-Pad202)") (class "Default")
      (node (ref "U1") (pin "202") (pinfunction "I/O_(122)_202") (pintype "bidirectional+no_connect"))
    )
    (net (code "249") (name "unconnected-(U1C-I{slash}O,_IRDY_(515)-Pad132)") (class "Default")
      (node (ref "U1") (pin "132") (pinfunction "I/O,_IRDY_(515)_132") (pintype "bidirectional+no_connect"))
    )
    (net (code "250") (name "unconnected-(U1C-I{slash}O,_VREF_(530)-Pad136)") (class "Default")
      (node (ref "U1") (pin "136") (pinfunction "I/O,_VREF_(530)_136") (pintype "bidirectional+no_connect"))
    )
    (net (code "251") (name "unconnected-(U1C-I{slash}O,_VREF_(566)-Pad150)") (class "Default")
      (node (ref "U1") (pin "150") (pinfunction "I/O,_VREF_(566)_150") (pintype "bidirectional+no_connect"))
    )
    (net (code "252") (name "unconnected-(U1C-I{slash}O_(518)-Pad133)") (class "Default")
      (node (ref "U1") (pin "133") (pinfunction "I/O_(518)_133") (pintype "bidirectional+no_connect"))
    )
    (net (code "253") (name "unconnected-(U1C-I{slash}O_(521)-Pad134)") (class "Default")
      (node (ref "U1") (pin "134") (pinfunction "I/O_(521)_134") (pintype "bidirectional+no_connect"))
    )
    (net (code "254") (name "unconnected-(U1C-I{slash}O_(536)-Pad139)") (class "Default")
      (node (ref "U1") (pin "139") (pinfunction "I/O_(536)_139") (pintype "bidirectional+no_connect"))
    )
    (net (code "255") (name "unconnected-(U1C-I{slash}O_(545)-Pad141)") (class "Default")
      (node (ref "U1") (pin "141") (pinfunction "I/O_(545)_141") (pintype "bidirectional+no_connect"))
    )
    (net (code "256") (name "unconnected-(U1C-I{slash}O_(557)-Pad148)") (class "Default")
      (node (ref "U1") (pin "148") (pinfunction "I/O_(557)_148") (pintype "bidirectional+no_connect"))
    )
    (net (code "257") (name "unconnected-(U1C-I{slash}O_(575)-Pad152)") (class "Default")
      (node (ref "U1") (pin "152") (pinfunction "I/O_(575)_152") (pintype "bidirectional+no_connect"))
    )
    (net (code "258") (name "unconnected-(U1C-I{slash}O_(D1)_(551)-Pad146)") (class "Default")
      (node (ref "U1") (pin "146") (pinfunction "I/O_(D1)_(551)_146") (pintype "bidirectional+no_connect"))
    )
    (net (code "259") (name "unconnected-(U1C-I{slash}O_(D3)_(527)-Pad135)") (class "Default")
      (node (ref "U1") (pin "135") (pinfunction "I/O_(D3)_(527)_135") (pintype "bidirectional+no_connect"))
    )
    (net (code "260") (name "unconnected-(U1C-I{slash}O_(DOUT,_BUSY)_(584)-Pad154)") (class "Default")
      (node (ref "U1") (pin "154") (pinfunction "I/O_(DOUT,_BUSY)_(584)_154") (pintype "bidirectional+no_connect"))
    )
    (net (code "261") (name "unconnected-(U1D-I{slash}O,_VREF_(497)-Pad125)") (class "Default")
      (node (ref "U1") (pin "125") (pinfunction "I/O,_VREF_(497)_125") (pintype "bidirectional+no_connect"))
    )
    (net (code "262") (name "unconnected-(U1D-I{slash}O_(458)-Pad110)") (class "Default")
      (node (ref "U1") (pin "110") (pinfunction "I/O_(458)_110") (pintype "bidirectional+no_connect"))
    )
    (net (code "263") (name "unconnected-(U1D-I{slash}O_(464)-Pad112)") (class "Default")
      (node (ref "U1") (pin "112") (pinfunction "I/O_(464)_112") (pintype "bidirectional+no_connect"))
    )
    (net (code "264") (name "unconnected-(U1D-I{slash}O_(473)-Pad114)") (class "Default")
      (node (ref "U1") (pin "114") (pinfunction "I/O_(473)_114") (pintype "bidirectional+no_connect"))
    )
    (net (code "265") (name "unconnected-(U1D-I{slash}O_(482)-Pad120)") (class "Default")
      (node (ref "U1") (pin "120") (pinfunction "I/O_(482)_120") (pintype "bidirectional+no_connect"))
    )
    (net (code "266") (name "unconnected-(U1D-I{slash}O_(491)-Pad122)") (class "Default")
      (node (ref "U1") (pin "122") (pinfunction "I/O_(491)_122") (pintype "bidirectional+no_connect"))
    )
    (net (code "267") (name "unconnected-(U1D-I{slash}O_(506)-Pad127)") (class "Default")
      (node (ref "U1") (pin "127") (pinfunction "I/O_(506)_127") (pintype "bidirectional+no_connect"))
    )
    (net (code "268") (name "unconnected-(U1D-I{slash}O_(D7)_(446)-Pad108)") (class "Default")
      (node (ref "U1") (pin "108") (pinfunction "I/O_(D7)_(446)_108") (pintype "bidirectional+no_connect"))
    )
    (net (code "269") (name "unconnected-(U1E-I{slash}O,_VREF_(382)-Pad84)") (class "Default")
      (node (ref "U1") (pin "84") (pinfunction "I/O,_VREF_(382)_84") (pintype "bidirectional+no_connect"))
    )
    (net (code "270") (name "unconnected-(U1E-I{slash}O_(370)-Pad81)") (class "Default")
      (node (ref "U1") (pin "81") (pinfunction "I/O_(370)_81") (pintype "bidirectional+no_connect"))
    )
    (net (code "271") (name "unconnected-(U1E-I{slash}O_(373)-Pad82)") (class "Default")
      (node (ref "U1") (pin "82") (pinfunction "I/O_(373)_82") (pintype "bidirectional+no_connect"))
    )
    (net (code "272") (name "unconnected-(U1E-I{slash}O_(379)-Pad83)") (class "Default")
      (node (ref "U1") (pin "83") (pinfunction "I/O_(379)_83") (pintype "bidirectional+no_connect"))
    )
    (net (code "273") (name "unconnected-(U1E-I{slash}O_(421)-Pad99)") (class "Default")
      (node (ref "U1") (pin "99") (pinfunction "I/O_(421)_99") (pintype "bidirectional+no_connect"))
    )
    (net (code "274") (name "unconnected-(U1E-I{slash}O_(433)-Pad101)") (class "Default")
      (node (ref "U1") (pin "101") (pinfunction "I/O_(433)_101") (pintype "bidirectional+no_connect"))
    )
    (net (code "275") (name "unconnected-(U1F-I{slash}O,_VREF_(347)-Pad73)") (class "Default")
      (node (ref "U1") (pin "73") (pinfunction "I/O,_VREF_(347)_73") (pintype "bidirectional+no_connect"))
    )
    (net (code "276") (name "unconnected-(U1F-I{slash}O_(314)-Pad60)") (class "Default")
      (node (ref "U1") (pin "60") (pinfunction "I/O_(314)_60") (pintype "bidirectional+no_connect"))
    )
    (net (code "277") (name "unconnected-(U1F-I{slash}O_(332)-Pad68)") (class "Default")
      (node (ref "U1") (pin "68") (pinfunction "I/O_(332)_68") (pintype "bidirectional+no_connect"))
    )
    (net (code "278") (name "unconnected-(U1F-I{slash}O_(338)-Pad69)") (class "Default")
      (node (ref "U1") (pin "69") (pinfunction "I/O_(338)_69") (pintype "bidirectional+no_connect"))
    )
    (net (code "279") (name "unconnected-(U1F-I{slash}O_(341)-Pad70)") (class "Default")
      (node (ref "U1") (pin "70") (pinfunction "I/O_(341)_70") (pintype "bidirectional+no_connect"))
    )
    (net (code "280") (name "unconnected-(U1F-I{slash}O_(344)-Pad71)") (class "Default")
      (node (ref "U1") (pin "71") (pinfunction "I/O_(344)_71") (pintype "bidirectional+no_connect"))
    )
    (net (code "281") (name "unconnected-(U1F-I{slash}O_(350)-Pad74)") (class "Default")
      (node (ref "U1") (pin "74") (pinfunction "I/O_(350)_74") (pintype "bidirectional+no_connect"))
    )
    (net (code "282") (name "unconnected-(U1F-I{slash}O_(356)-Pad75)") (class "Default")
      (node (ref "U1") (pin "75") (pinfunction "I/O_(356)_75") (pintype "bidirectional+no_connect"))
    )
    (net (code "283") (name "unconnected-(U1G-I{slash}O_(266)-Pad44)") (class "Default")
      (node (ref "U1") (pin "44") (pinfunction "I/O_(266)_44") (pintype "bidirectional+no_connect"))
    )
    (net (code "284") (name "unconnected-(U1H-I{slash}O_(167)-Pad7)") (class "Default")
      (node (ref "U1") (pin "7") (pinfunction "I/O_(167)_7") (pintype "bidirectional+no_connect"))
    )
    (net (code "285") (name "unconnected-(U1I-GCK2_(72)-Pad182)") (class "Default")
      (node (ref "U1") (pin "182") (pinfunction "GCK2_(72)_182") (pintype "input+no_connect"))
    )
    (net (code "286") (name "unconnected-(U1J-NC-Pad55)") (class "Default")
      (node (ref "U1") (pin "55") (pinfunction "NC_55") (pintype "passive+no_connect"))
    )
    (net (code "287") (name "unconnected-(U1J-NC-Pad56)") (class "Default")
      (node (ref "U1") (pin "56") (pinfunction "NC_56") (pintype "passive+no_connect"))
    )
    (net (code "288") (name "unconnected-(U2-D1-Pad16)") (class "Default")
      (node (ref "U2") (pin "16") (pinfunction "D1_16") (pintype "tri_state+no_connect"))
    )
    (net (code "289") (name "unconnected-(U2-D2-Pad2)") (class "Default")
      (node (ref "U2") (pin "2") (pinfunction "D2_2") (pintype "tri_state+no_connect"))
    )
    (net (code "290") (name "unconnected-(U2-D3-Pad15)") (class "Default")
      (node (ref "U2") (pin "15") (pinfunction "D3_15") (pintype "tri_state+no_connect"))
    )
    (net (code "291") (name "unconnected-(U2-D5-Pad14)") (class "Default")
      (node (ref "U2") (pin "14") (pinfunction "D5_14") (pintype "tri_state+no_connect"))
    )
    (net (code "292") (name "unconnected-(U2-D6-Pad9)") (class "Default")
      (node (ref "U2") (pin "9") (pinfunction "D6_9") (pintype "tri_state+no_connect"))
    )
    (net (code "293") (name "unconnected-(U2-D7-Pad12)") (class "Default")
      (node (ref "U2") (pin "12") (pinfunction "D7_12") (pintype "tri_state+no_connect"))
    )
    (net (code "294") (name "unconnected-(U2-~{CEO}-Pad13)") (class "Default")
      (node (ref "U2") (pin "13") (pinfunction "~{CEO}_13") (pintype "output+no_connect"))
    )
    (net (code "295") (name "unconnected-(U4-WDI-Pad4)") (class "Default")
      (node (ref "U4") (pin "4") (pinfunction "WDI_4") (pintype "passive+no_connect"))
    )
  )
)
